# soap-disp-20210413-16Channel.net
KiCad netlist of a schematic drawn in EasyEDA
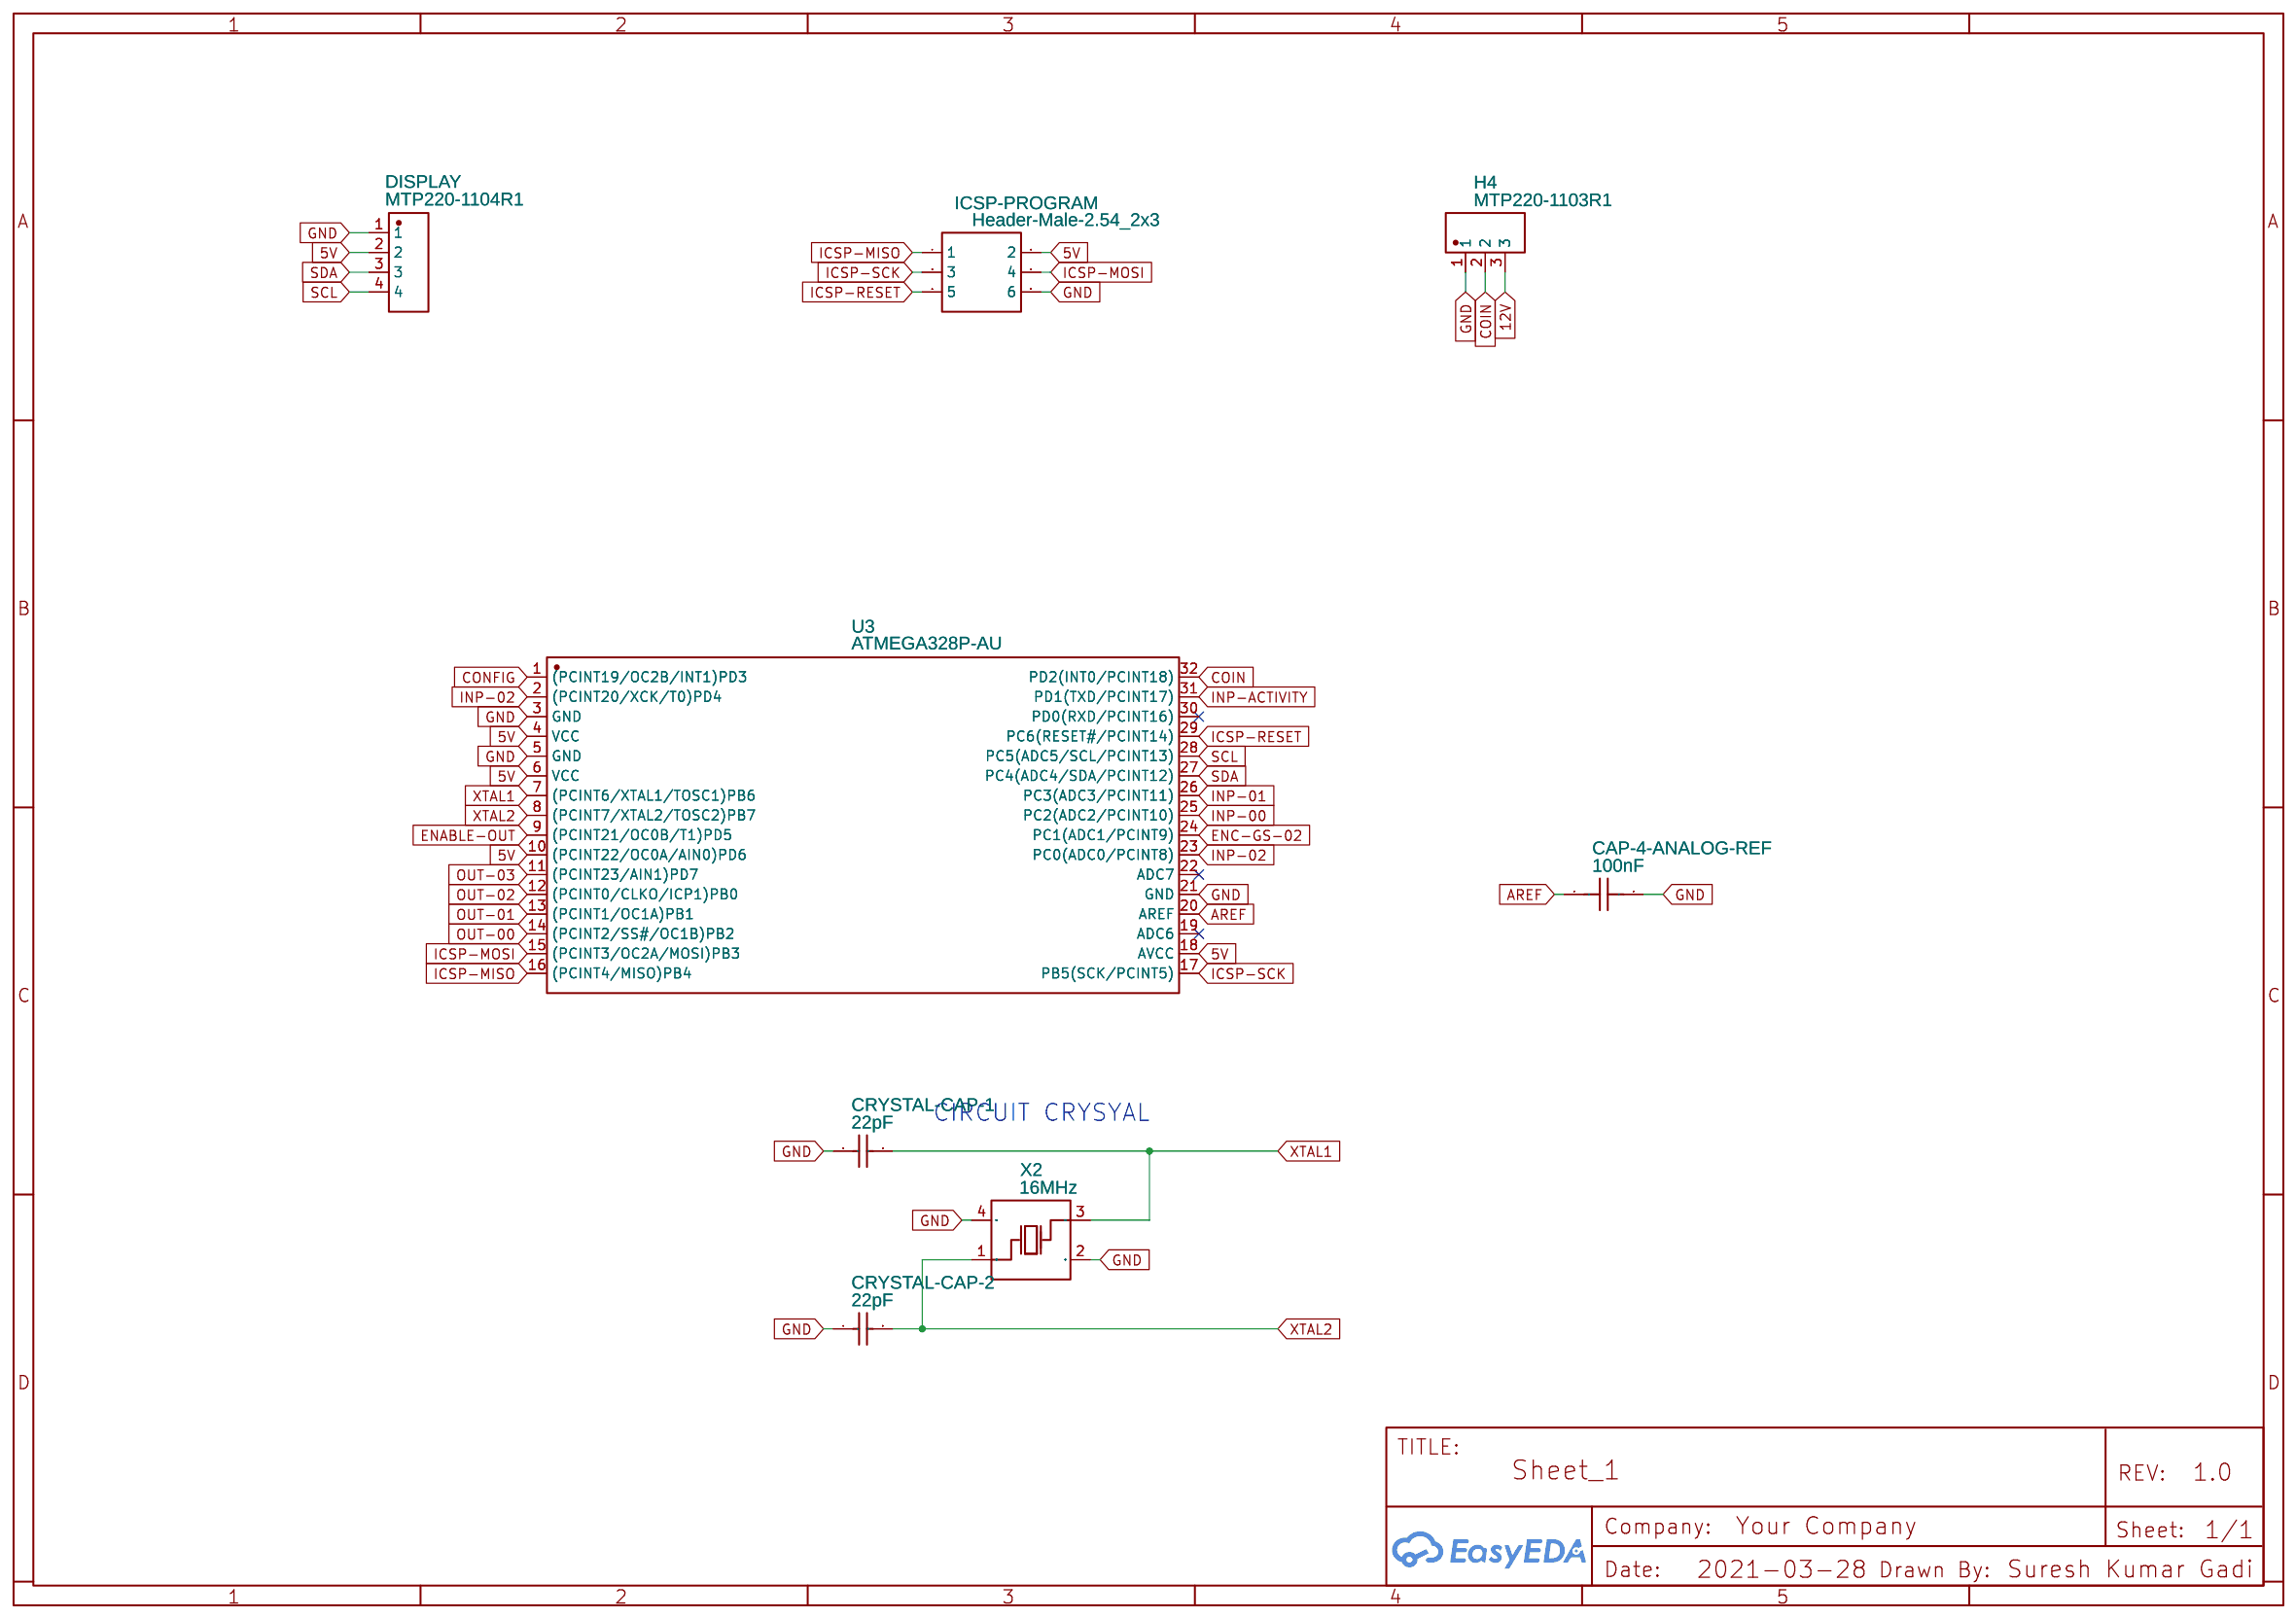
[diagram p0: Computer]
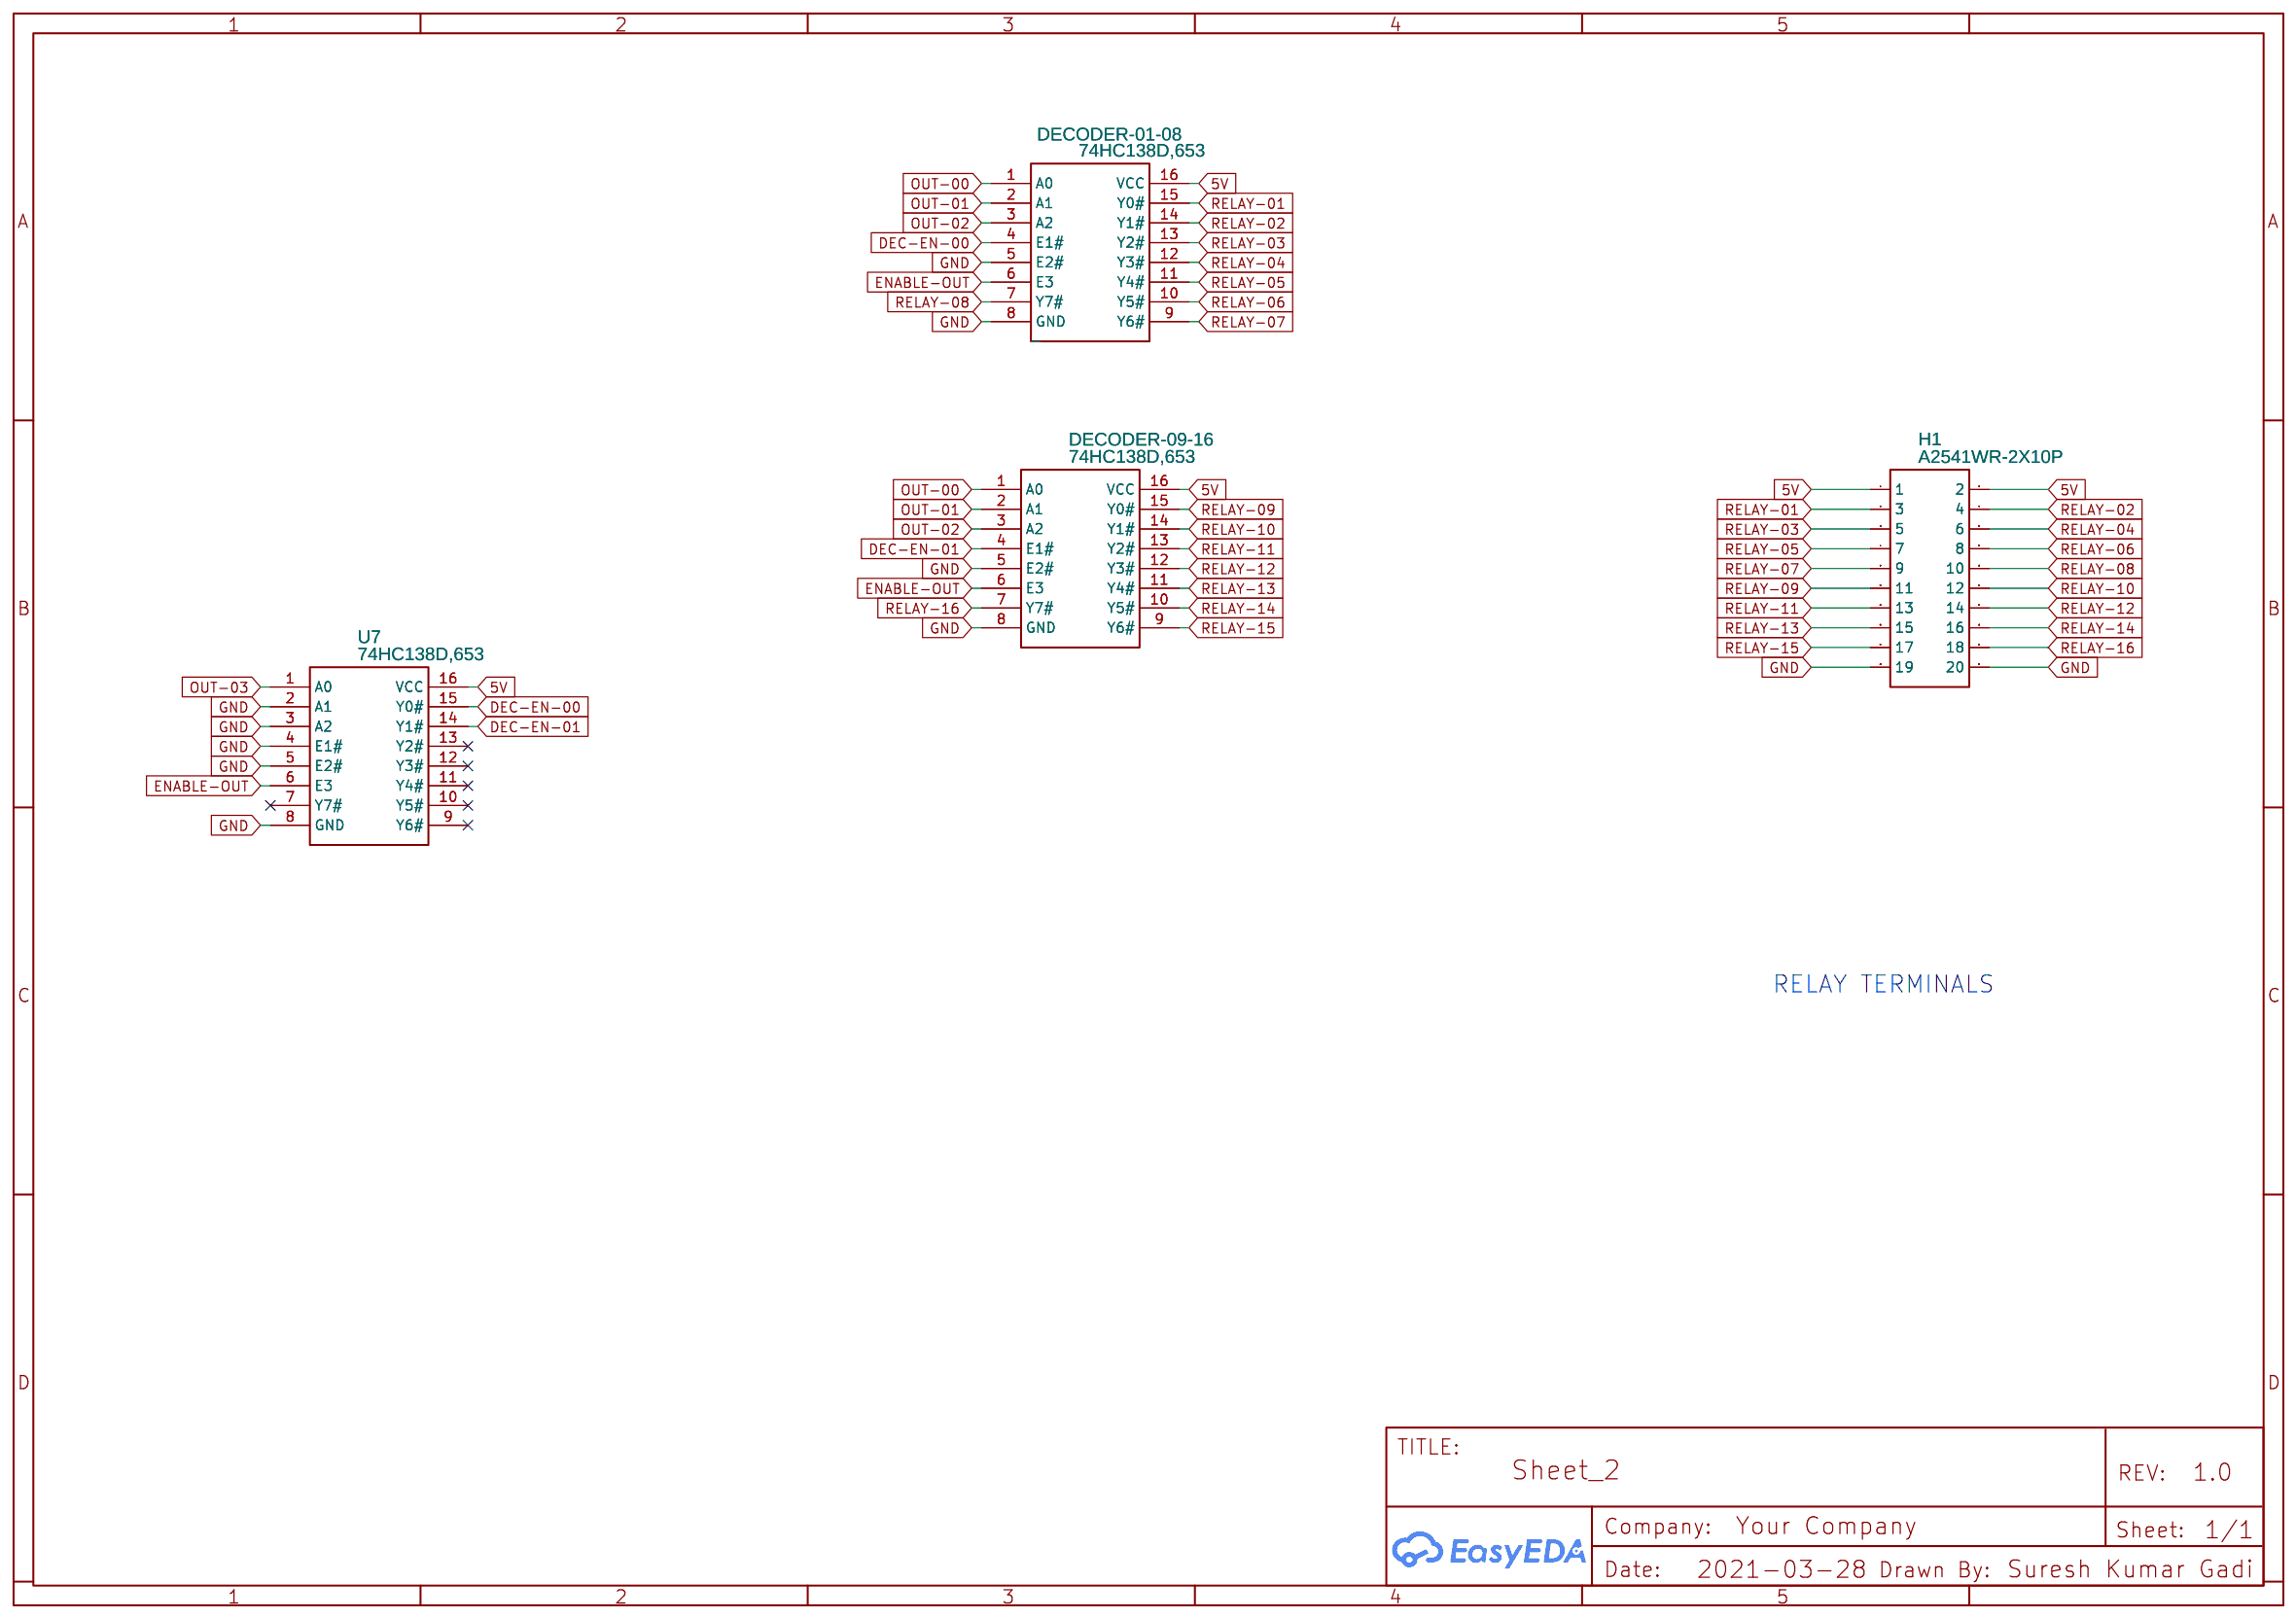
[diagram p1: Relays]
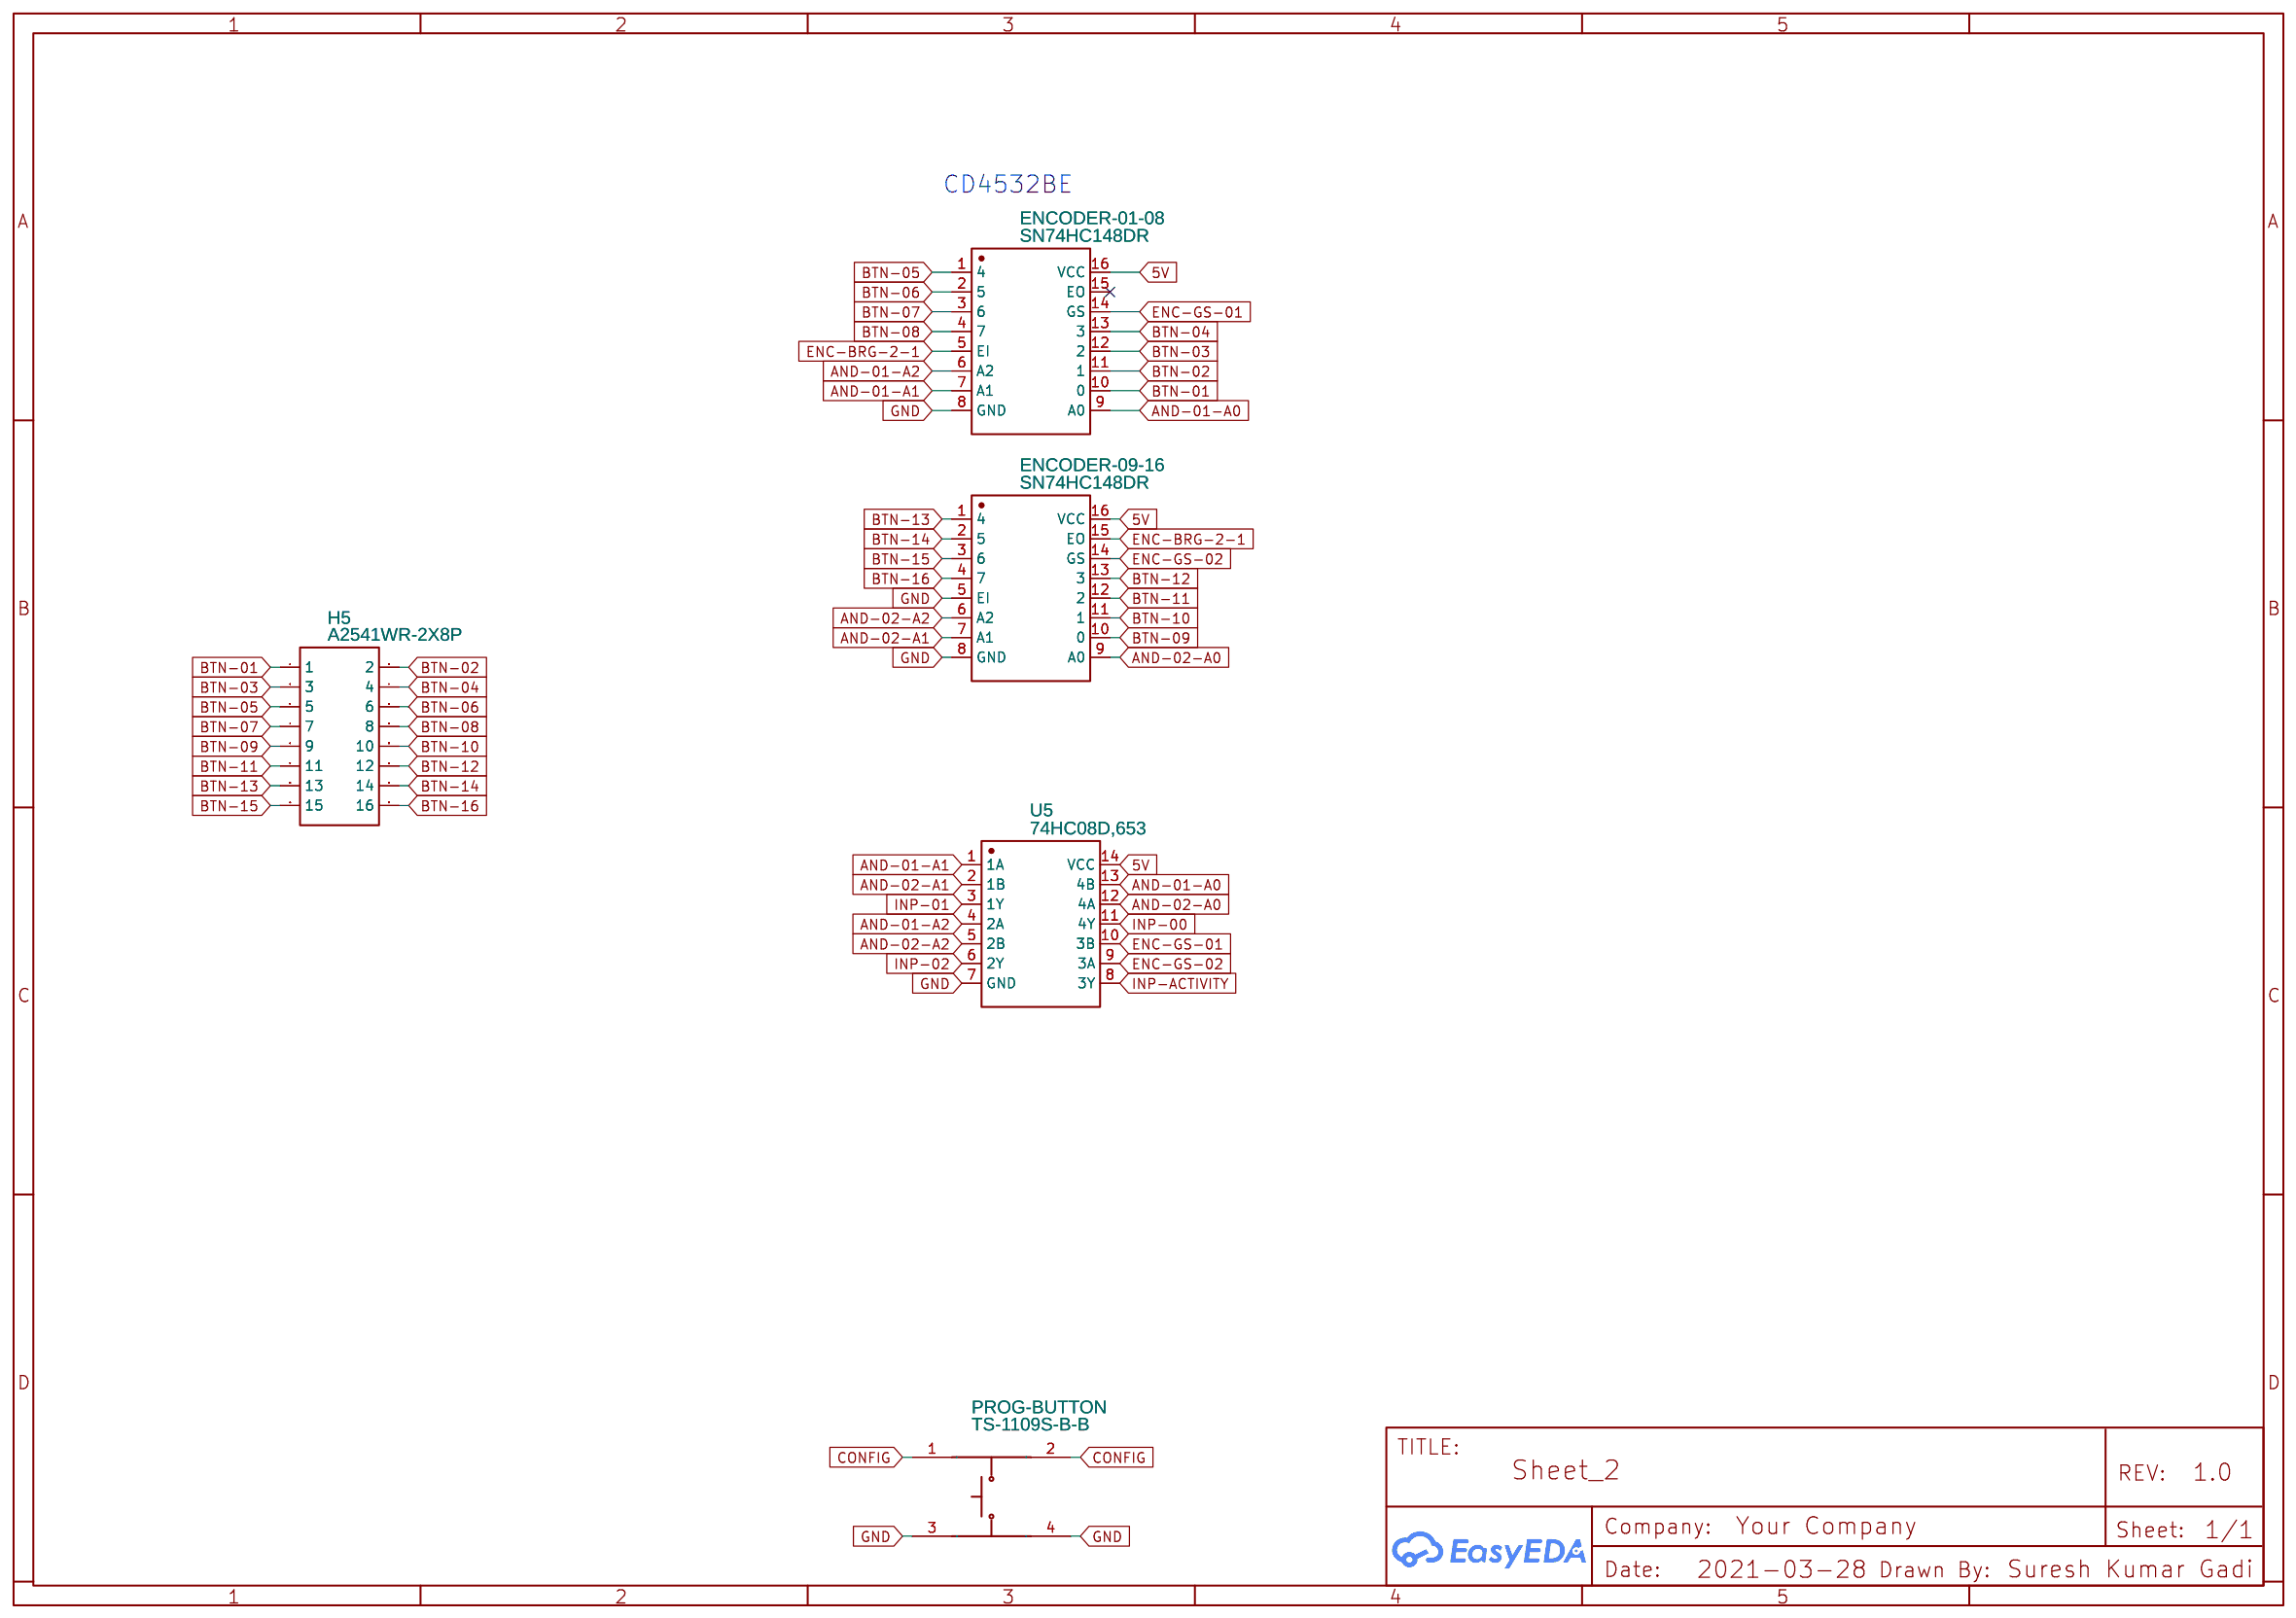
[diagram p2: Buttons]
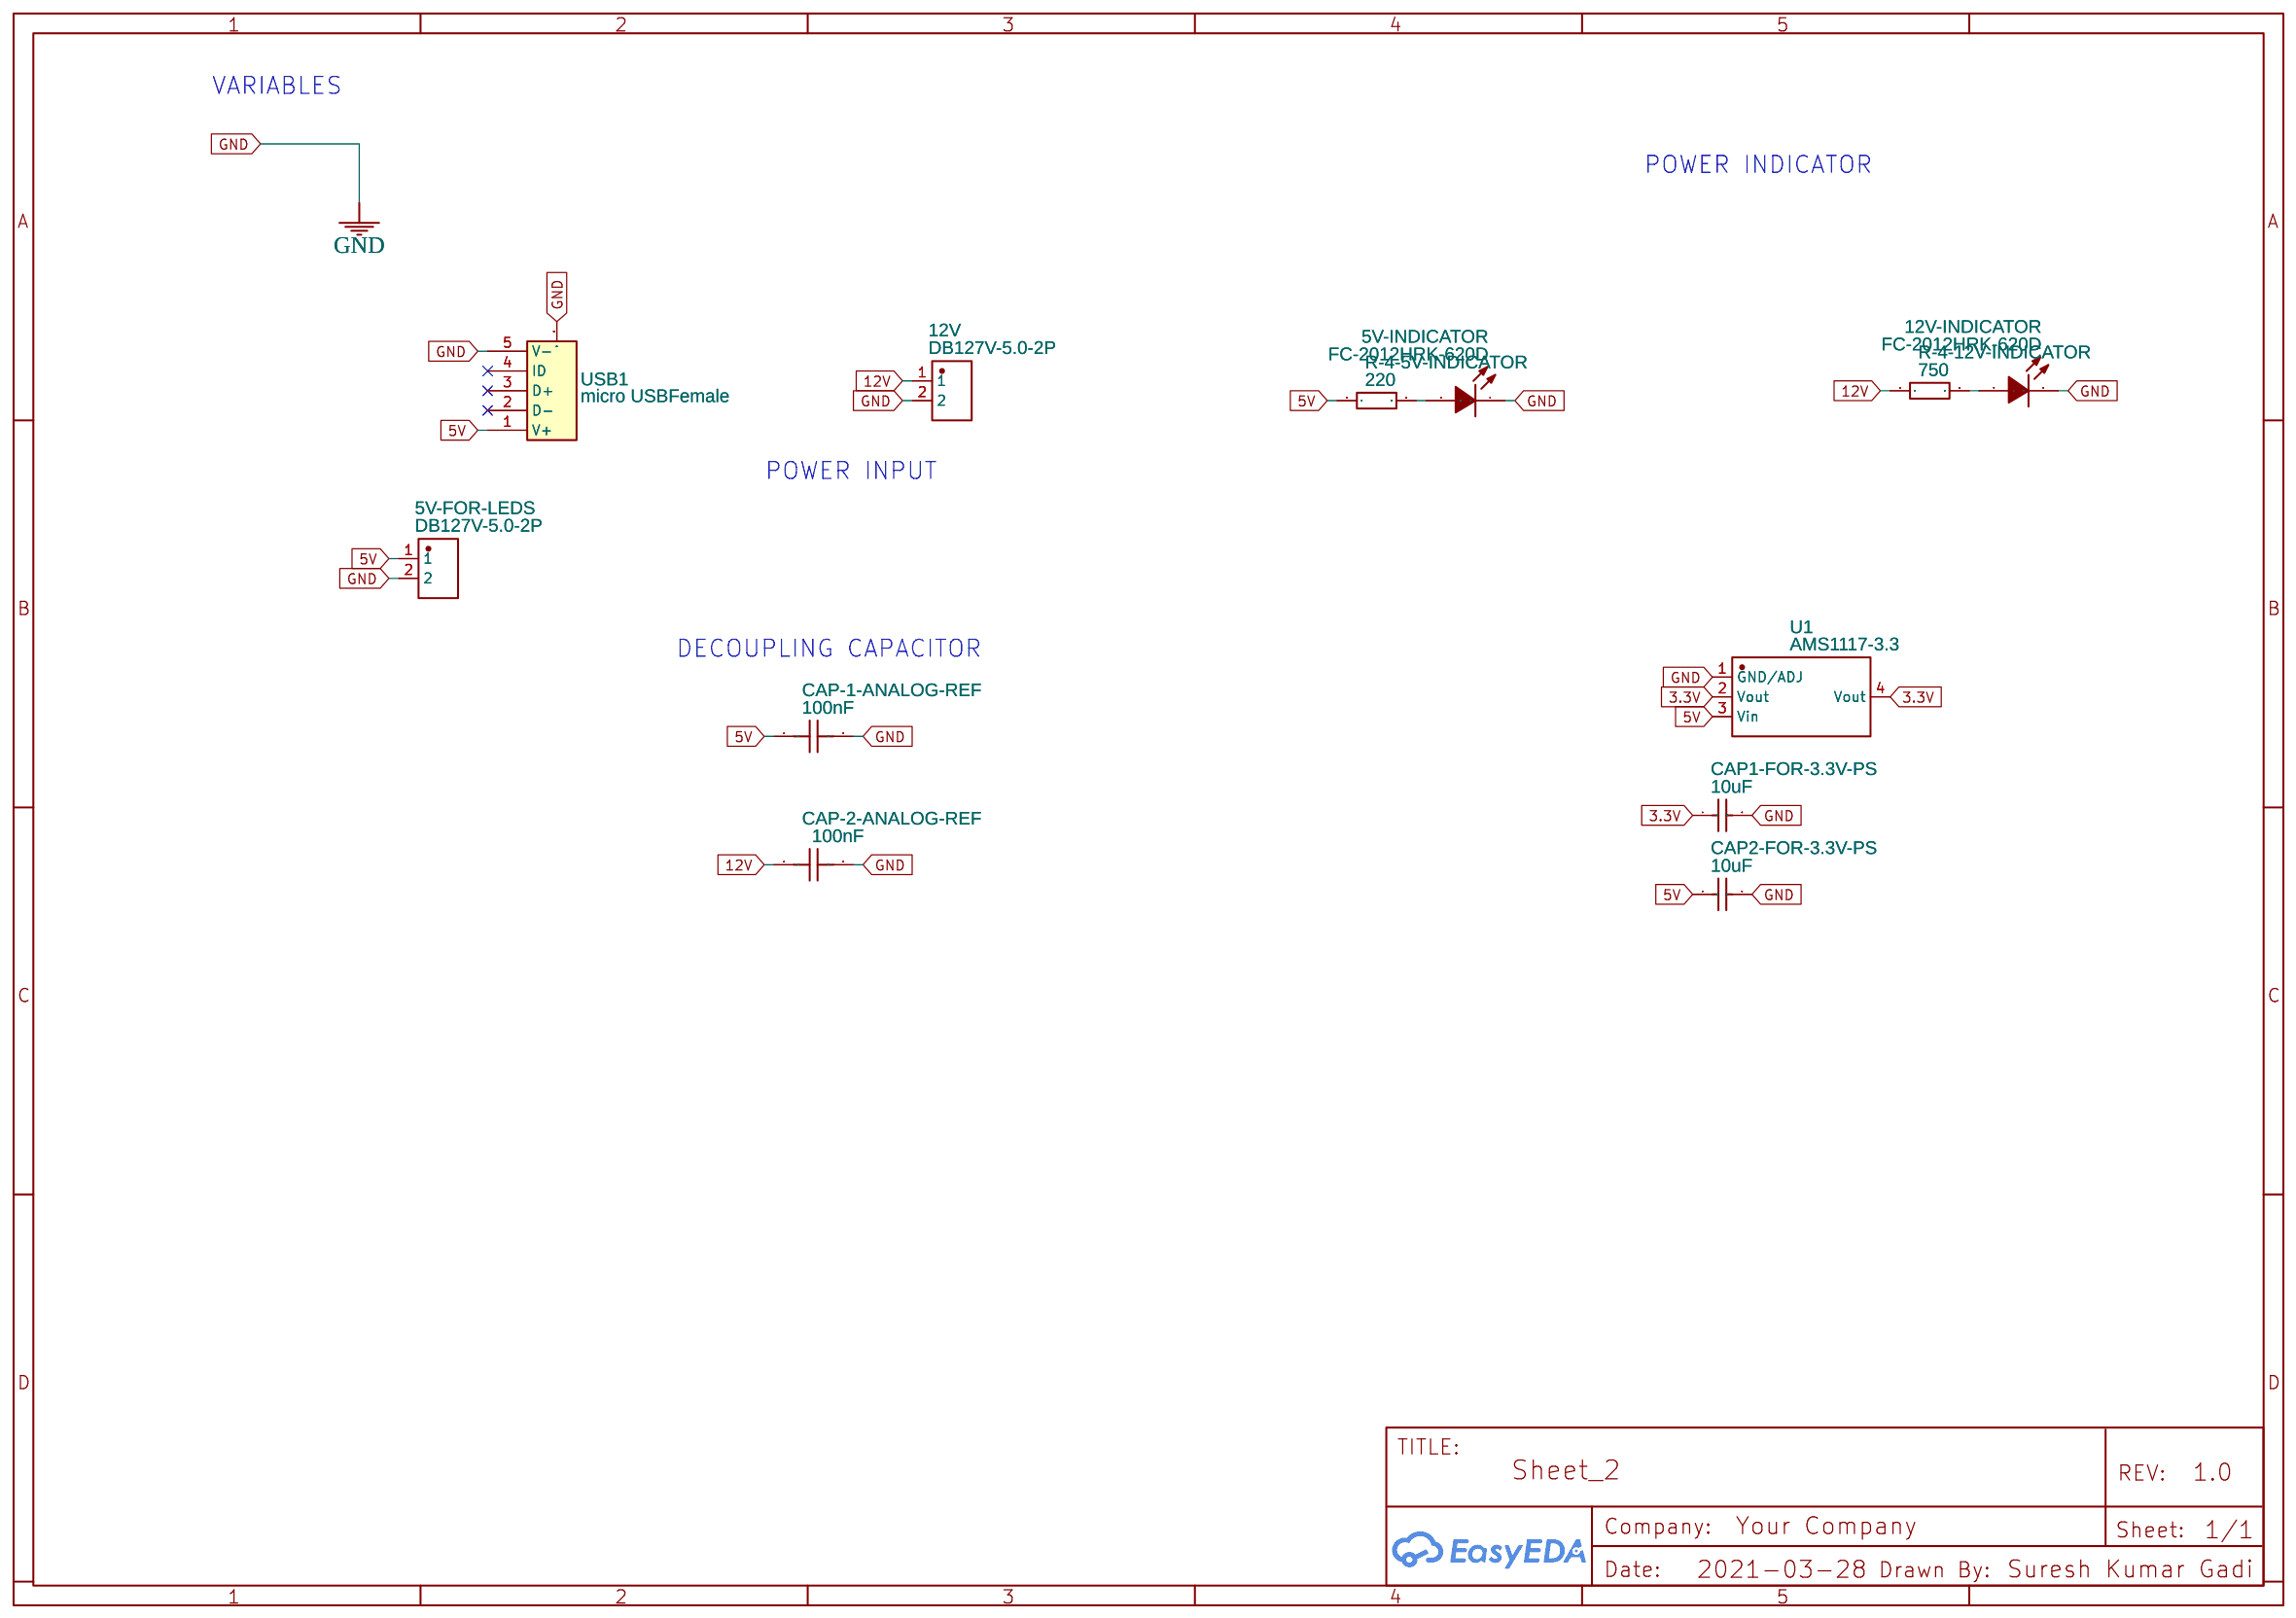
[diagram p3: Power]
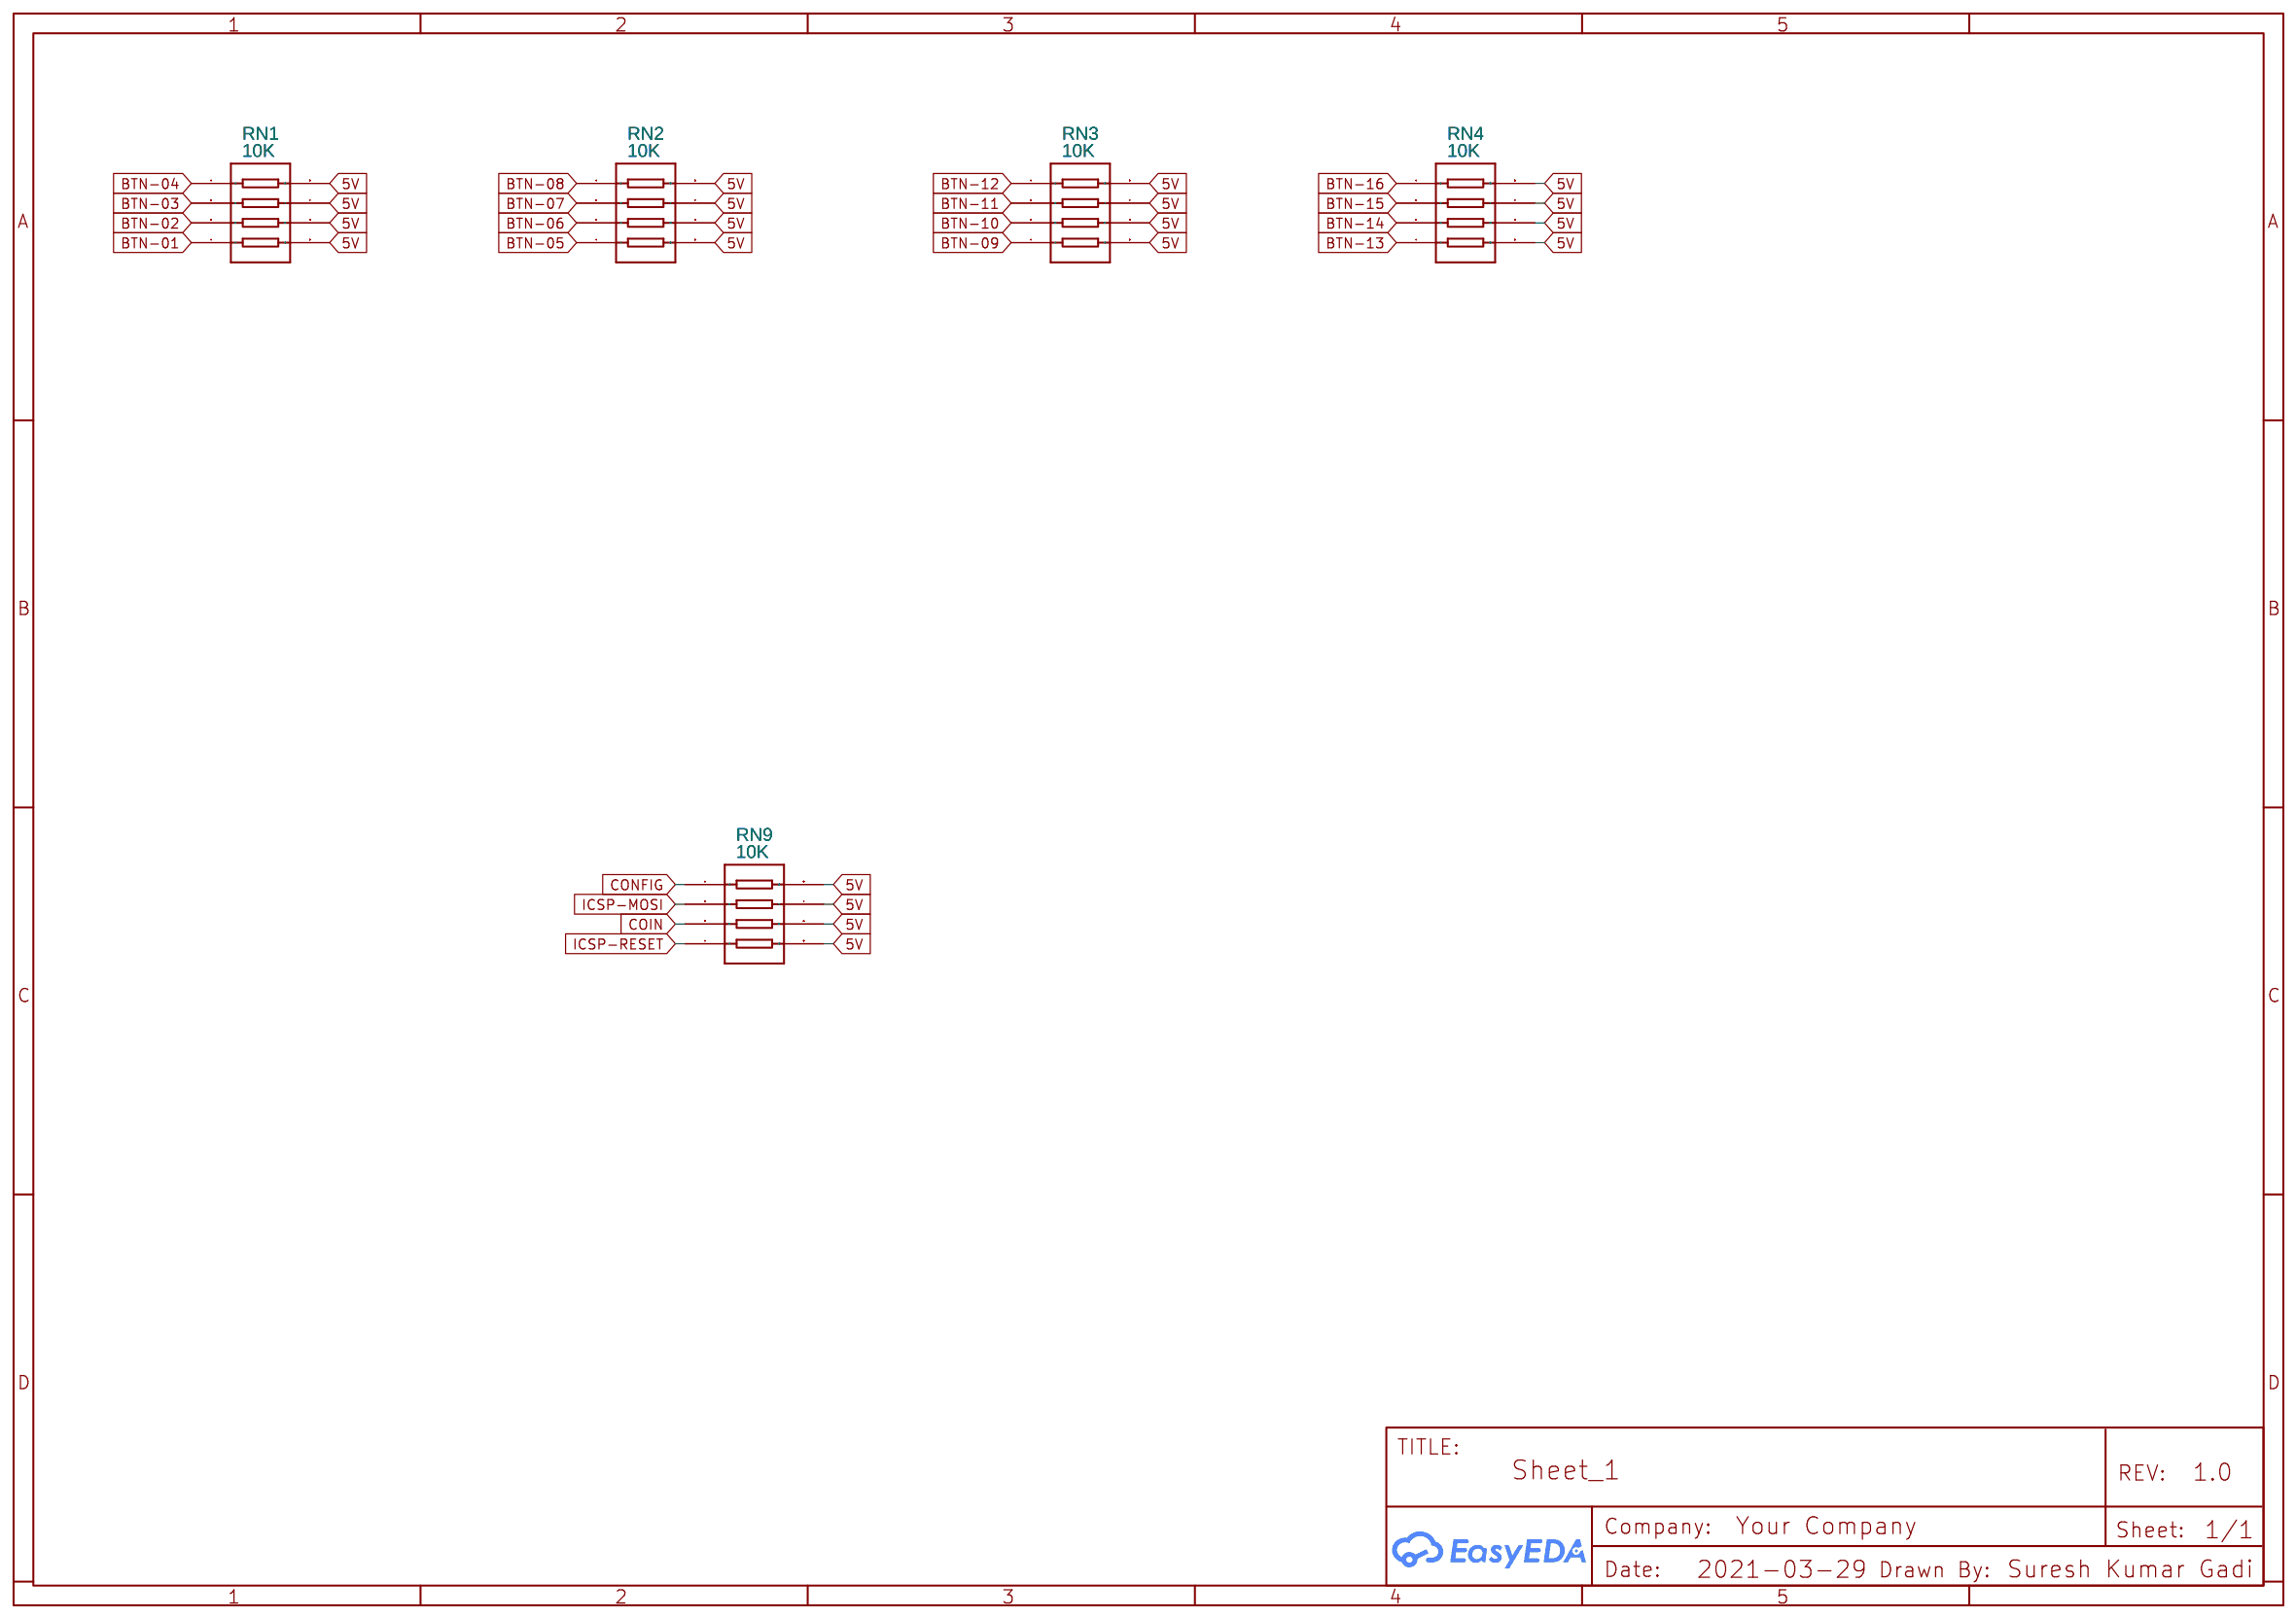
[diagram p4: Pull up-down]
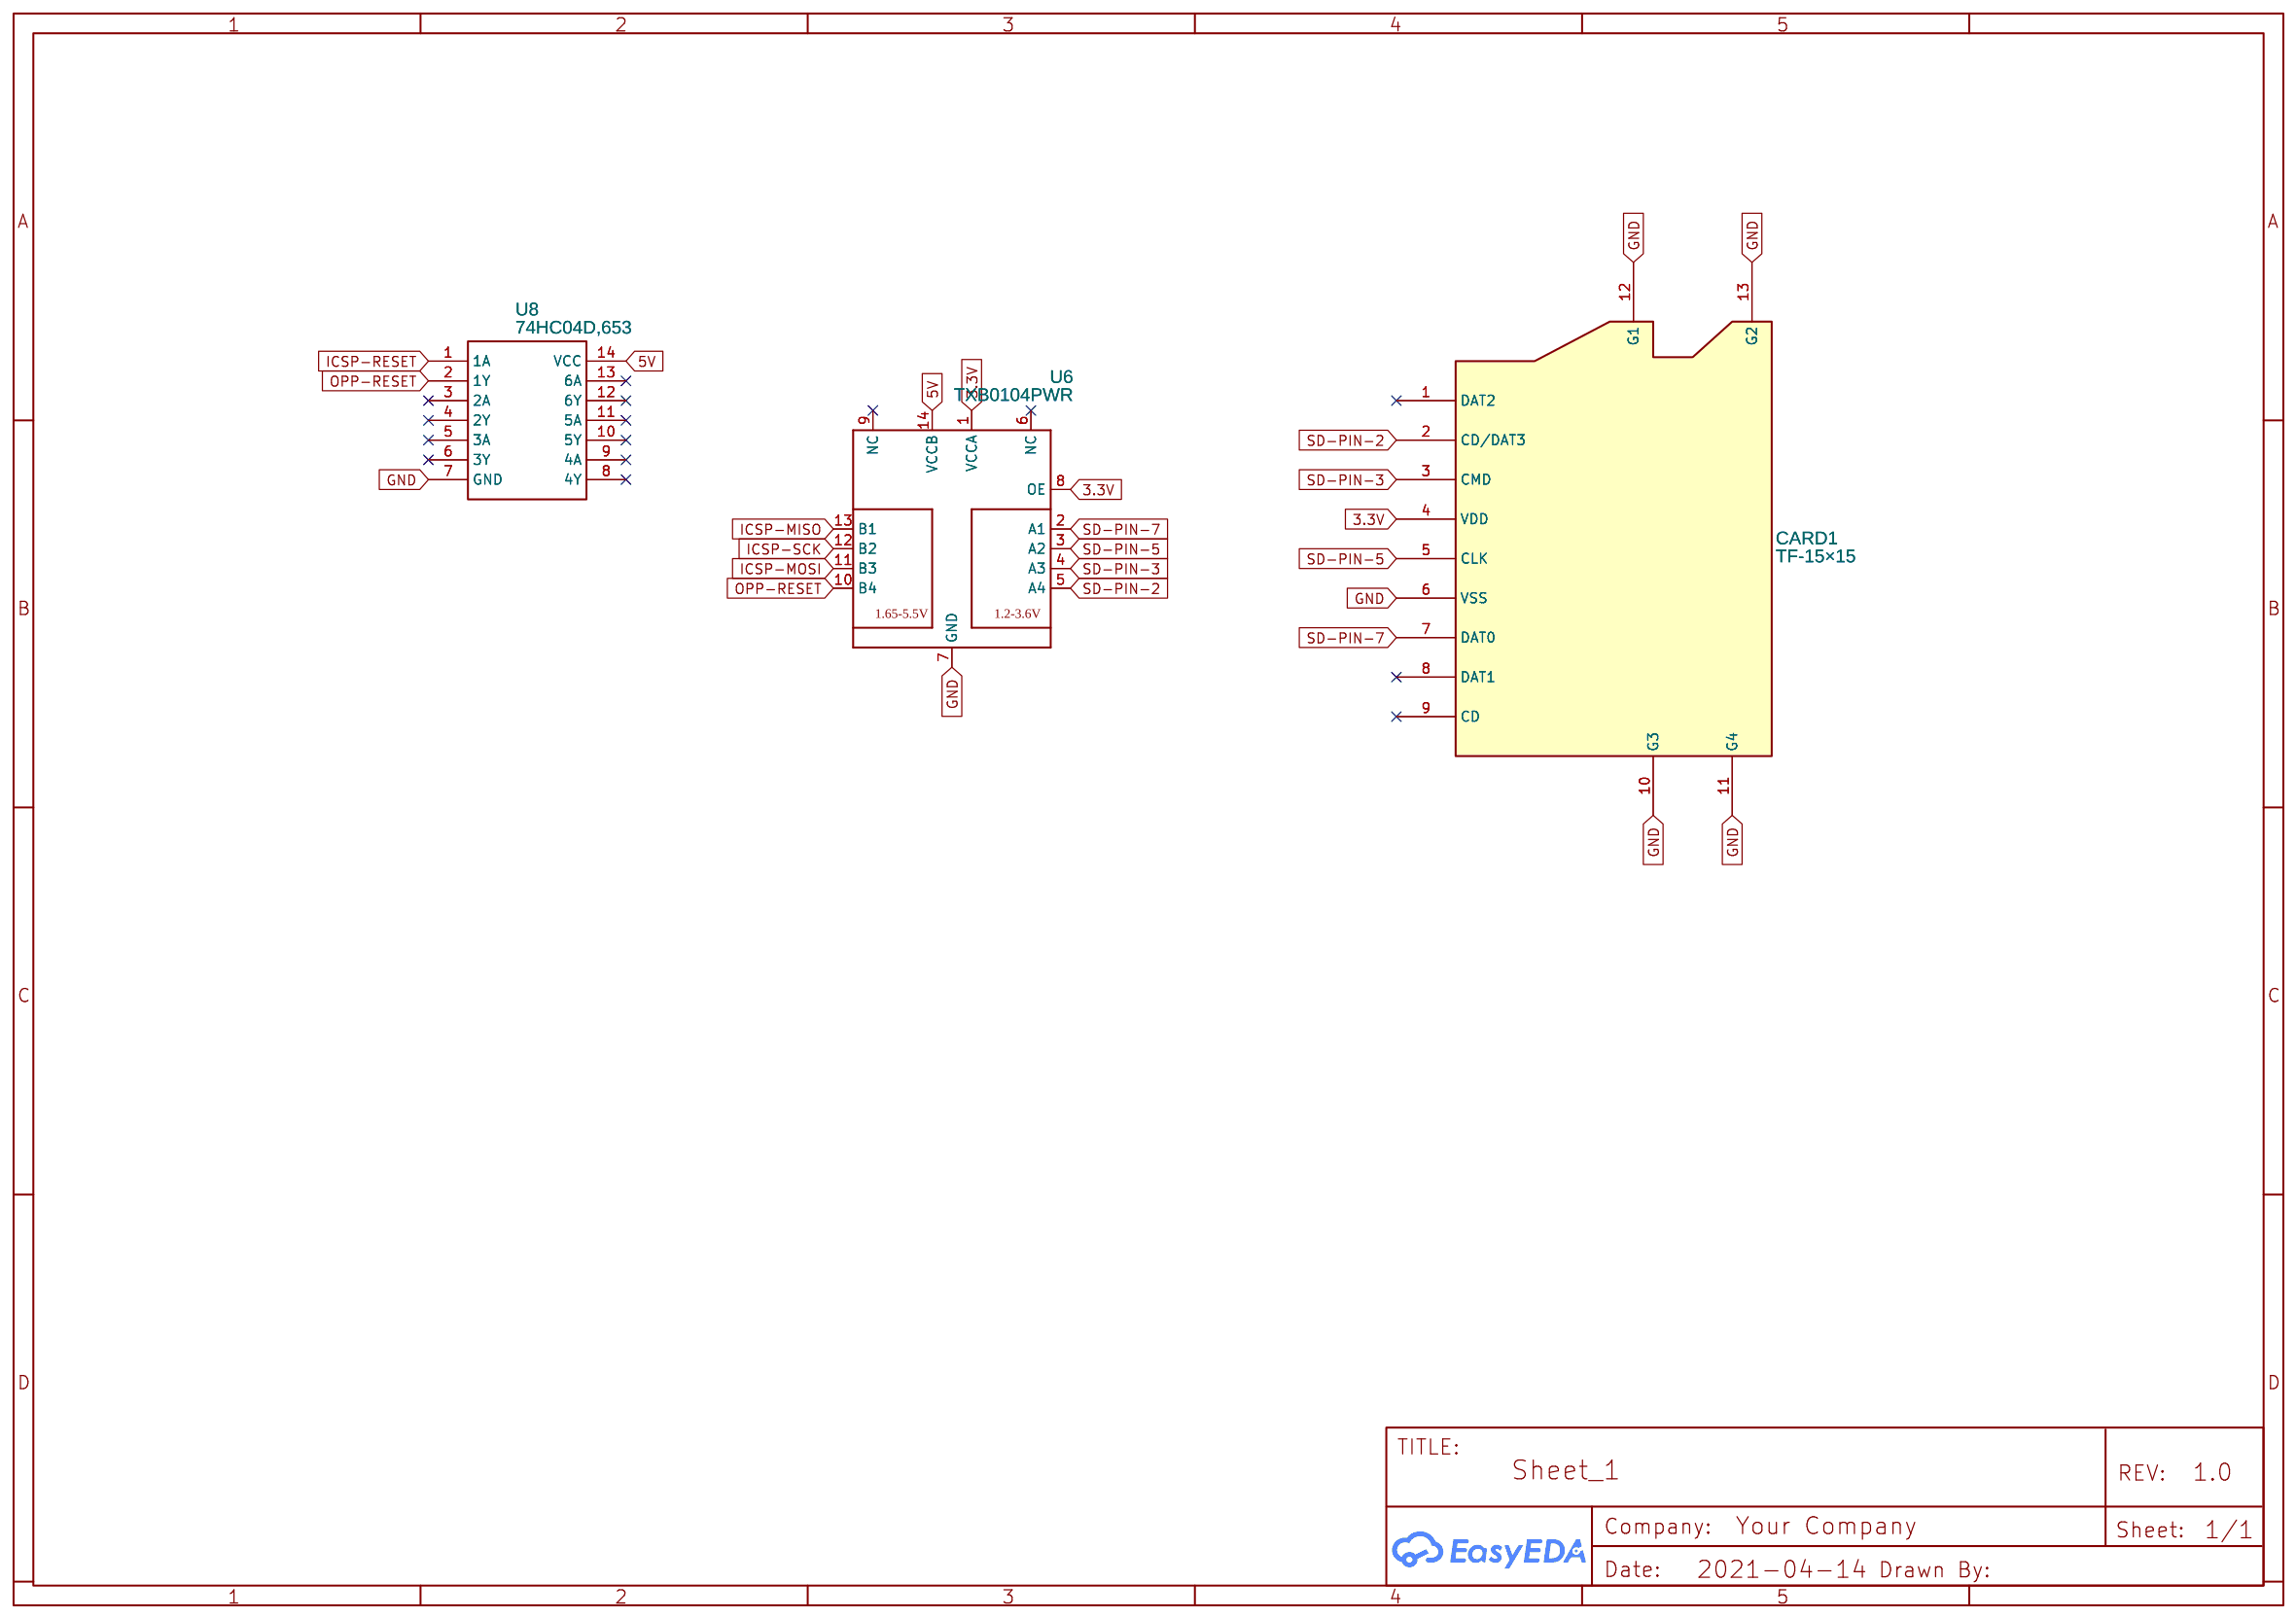
[diagram p5: SD Card]

(export (version "E")
  (design (tool "Eeschema 10.0.6"))
  (components
    (comp (ref "CAP-4-ANALOG-REF")
      (value "100nF")
      (fields
        (field (name "BOM_Manufacturer Part") "CC0603KRX7R9BB104")
        (field (name "BOM_Supplier Part") "C14663")
      )
      (libsource (lib "") (part "CC0603KRX7R9BB104"))
    )
    (comp (ref "CRYSTAL-CAP-1")
      (value "22pF")
      (fields
        (field (name "BOM_Manufacturer Part") "CL21C220JBANNNC")
        (field (name "BOM_Supplier Part") "C1804")
      )
      (libsource (lib "") (part "CL21C220JBANNNC"))
    )
    (comp (ref "CRYSTAL-CAP-2")
      (value "22pF")
      (fields
        (field (name "BOM_Manufacturer Part") "CL21C220JBANNNC")
        (field (name "BOM_Supplier Part") "C1804")
      )
      (libsource (lib "") (part "CL21C220JBANNNC"))
    )
    (comp (ref "DISPLAY")
      (value "MTP220-1104R1")
      (fields (field (name "BOM_Supplier Part") "C376098"))
      (libsource (lib "") (part "MTP220-1104R1"))
    )
    (comp (ref "H4")
      (value "MTP220-1103R1")
      (fields (field (name "BOM_Supplier Part") "C376097"))
      (libsource (lib "") (part "MTP220-1103R1"))
    )
    (comp (ref "ICSP-PROGRAM")
      (value "Header-Male-2.54_2x3")
      (fields (field (name "BOM_Supplier Part") "C65114"))
      (libsource (lib "") (part "Header-Male-2.54_2x3"))
    )
    (comp (ref "U3")
      (value "ATMEGA328P-AU")
      (fields (field (name "BOM_Supplier Part") "C14877"))
      (libsource (lib "") (part "ATMEGA328P-AU"))
    )
    (comp (ref "X2")
      (value "16MHz")
      (fields
        (field (name "BOM_Manufacturer Part") "X322516MLB4SI")
        (field (name "BOM_Supplier Part") "C13738")
      )
      (libsource (lib "") (part "X322516MLB4SI"))
    )
    (comp (ref "DECODER-01-08")
      (value "74HC138D,653")
      (fields (field (name "BOM_Supplier Part") "C5602"))
      (libsource (lib "") (part "74HC138D,653"))
    )
    (comp (ref "DECODER-09-16")
      (value "74HC138D,653")
      (fields (field (name "BOM_Supplier Part") "C5602"))
      (libsource (lib "") (part "74HC138D,653_2"))
    )
    (comp (ref "H1")
      (value "A2541WR-2X10P")
      (fields
        (field (name "BOM_Manufacturer Part") "A2541WR-2x10P")
        (field (name "BOM_Supplier Part") "C239341")
      )
      (libsource (lib "") (part "A2541WR-2X10P"))
    )
    (comp (ref "U7")
      (value "74HC138D,653")
      (fields (field (name "BOM_Supplier Part") "C5602"))
      (libsource (lib "") (part "74HC138D,653_1"))
    )
    (comp (ref "ENCODER-01-08")
      (value "SN74HC148DR")
      (fields (field (name "BOM_Supplier Part") "C6819"))
      (libsource (lib "") (part "SN74HC148DR_1"))
    )
    (comp (ref "ENCODER-09-16")
      (value "SN74HC148DR")
      (fields (field (name "BOM_Supplier Part") "C6819"))
      (libsource (lib "") (part "SN74HC148DR"))
    )
    (comp (ref "H5")
      (value "A2541WR-2X8P")
      (fields
        (field (name "BOM_Manufacturer Part") "A2541WR-2x8P")
        (field (name "BOM_Supplier Part") "C239339")
      )
      (libsource (lib "") (part "A2541WR-2X8P"))
    )
    (comp (ref "PROG-BUTTON")
      (value "TS-1109S-B-B")
      (fields (field (name "BOM_Supplier Part") "C480315"))
      (libsource (lib "") (part "TS-1109S-B-B"))
    )
    (comp (ref "U5")
      (value "74HC08D,653")
      (fields (field (name "BOM_Supplier Part") "C5593"))
      (libsource (lib "") (part "74HC08D,653"))
    )
    (comp (ref "5V-FOR-LEDS")
      (value "DB127V-5.0-2P")
      (fields (field (name "BOM_Supplier Part") "C395885"))
      (libsource (lib "") (part "DB127V-5.0-2P"))
    )
    (comp (ref "5V-INDICATOR")
      (value "FC-2012HRK-620D")
      (fields (field (name "BOM_Supplier Part") "C84256"))
      (libsource (lib "") (part "FC-2012HRK-620D"))
    )
    (comp (ref "12V")
      (value "DB127V-5.0-2P")
      (fields (field (name "BOM_Supplier Part") "C395885"))
      (libsource (lib "") (part "DB127V-5.0-2P_1"))
    )
    (comp (ref "12V-INDICATOR")
      (value "FC-2012HRK-620D")
      (fields (field (name "BOM_Supplier Part") "C84256"))
      (libsource (lib "") (part "FC-2012HRK-620D_1"))
    )
    (comp (ref "CAP-1-ANALOG-REF")
      (value "100nF")
      (fields
        (field (name "BOM_Manufacturer Part") "CC0603KRX7R9BB104")
        (field (name "BOM_Supplier Part") "C14663")
      )
      (libsource (lib "") (part "CC0603KRX7R9BB104_1"))
    )
    (comp (ref "CAP-2-ANALOG-REF")
      (value "100nF")
      (fields
        (field (name "BOM_Manufacturer Part") "CC0603KRX7R9BB104")
        (field (name "BOM_Supplier Part") "C14663")
      )
      (libsource (lib "") (part "CC0603KRX7R9BB104"))
    )
    (comp (ref "CAP1-FOR-3.3V-PS")
      (value "10uF")
      (fields
        (field (name "BOM_Manufacturer Part") "CL21A106KAYNNNE")
        (field (name "BOM_Supplier Part") "C15850")
      )
      (libsource (lib "") (part "CL21A106KAYNNNE"))
    )
    (comp (ref "CAP2-FOR-3.3V-PS")
      (value "10uF")
      (fields
        (field (name "BOM_Manufacturer Part") "CL21A106KAYNNNE")
        (field (name "BOM_Supplier Part") "C15850")
      )
      (libsource (lib "") (part "CL21A106KAYNNNE_1"))
    )
    (comp (ref "R-4-5V-INDICATOR")
      (value "220")
      (fields
        (field (name "BOM_Manufacturer Part") "0805W8F2200T5E")
        (field (name "BOM_Supplier Part") "C17557")
      )
      (libsource (lib "") (part "0805W8F2200T5E"))
    )
    (comp (ref "R-4-12V-INDICATOR")
      (value "750")
      (fields
        (field (name "BOM_Manufacturer Part") "1206W4F7500T5E")
        (field (name "BOM_Supplier Part") "C17985")
      )
      (libsource (lib "") (part "1206W4F7500T5E"))
    )
    (comp (ref "U1")
      (value "AMS1117-3.3")
      (fields (field (name "BOM_Supplier Part") "C6186"))
      (libsource (lib "") (part "AMS1117-3.3"))
    )
    (comp (ref "USB1")
      (value "micro USBFemale")
      (fields (field (name "BOM_Supplier Part") "C10418"))
      (libsource (lib "") (part "micro USBFemale"))
    )
    (comp (ref "RN1")
      (value "10K")
      (fields
        (field (name "BOM_Manufacturer Part") "4D03WGJ0103T5E")
        (field (name "BOM_Supplier Part") "C29718")
      )
      (libsource (lib "") (part "4D03WGJ0103T5E"))
    )
    (comp (ref "RN2")
      (value "10K")
      (fields
        (field (name "BOM_Manufacturer Part") "4D03WGJ0103T5E")
        (field (name "BOM_Supplier Part") "C29718")
      )
      (libsource (lib "") (part "4D03WGJ0103T5E"))
    )
    (comp (ref "RN3")
      (value "10K")
      (fields
        (field (name "BOM_Manufacturer Part") "4D03WGJ0103T5E")
        (field (name "BOM_Supplier Part") "C29718")
      )
      (libsource (lib "") (part "4D03WGJ0103T5E"))
    )
    (comp (ref "RN4")
      (value "10K")
      (fields
        (field (name "BOM_Manufacturer Part") "4D03WGJ0103T5E")
        (field (name "BOM_Supplier Part") "C29718")
      )
      (libsource (lib "") (part "4D03WGJ0103T5E"))
    )
    (comp (ref "RN9")
      (value "10K")
      (fields
        (field (name "BOM_Manufacturer Part") "4D03WGJ0103T5E")
        (field (name "BOM_Supplier Part") "C29718")
      )
      (libsource (lib "") (part "4D03WGJ0103T5E"))
    )
    (comp (ref "CARD1")
      (value "TF-15×15")
      (fields (field (name "BOM_Supplier Part") "C111196"))
      (libsource (lib "") (part "TF-15×15"))
    )
    (comp (ref "U6")
      (value "TXB0104PWR")
      (fields (field (name "BOM_Supplier Part") "C60708"))
      (libsource (lib "") (part "TXB0104PWR"))
    )
    (comp (ref "U8")
      (value "74HC04D,653")
      (fields (field (name "BOM_Supplier Part") "C5590"))
      (libsource (lib "") (part "74HC04D,653"))
    )
  )
  (nets
    (net (code "1") (name "3.3V") (class "Default")
      (node (ref "CAP1-FOR-3.3V-PS") (pin "1") (pinfunction "1_1") (pintype "input"))
      (node (ref "CARD1") (pin "4") (pinfunction "VDD_4") (pintype "input"))
      (node (ref "U1") (pin "2") (pinfunction "Vout_2") (pintype "unspecified"))
      (node (ref "U1") (pin "4") (pinfunction "Vout_4") (pintype "unspecified"))
      (node (ref "U6") (pin "1") (pinfunction "VCCA_1") (pintype "unspecified"))
      (node (ref "U6") (pin "8") (pinfunction "OE_8") (pintype "unspecified"))
    )
    (net (code "2") (name "5V") (class "Default")
      (node (ref "5V-FOR-LEDS") (pin "1") (pinfunction "1_1") (pintype "unspecified"))
      (node (ref "CAP-1-ANALOG-REF") (pin "1") (pinfunction "1_1") (pintype "unspecified"))
      (node (ref "CAP2-FOR-3.3V-PS") (pin "1") (pinfunction "1_1") (pintype "input"))
      (node (ref "DECODER-01-08") (pin "16") (pinfunction "VCC_16") (pintype "unspecified"))
      (node (ref "DECODER-09-16") (pin "16") (pinfunction "VCC_16") (pintype "unspecified"))
      (node (ref "DISPLAY") (pin "2") (pinfunction "2_2") (pintype "unspecified"))
      (node (ref "ENCODER-01-08") (pin "16") (pinfunction "VCC_16") (pintype "unspecified"))
      (node (ref "ENCODER-09-16") (pin "16") (pinfunction "VCC_16") (pintype "unspecified"))
      (node (ref "H1") (pin "1") (pinfunction "1_1") (pintype "unspecified"))
      (node (ref "H1") (pin "2") (pinfunction "2_2") (pintype "unspecified"))
      (node (ref "ICSP-PROGRAM") (pin "2") (pinfunction "2_2") (pintype "input"))
      (node (ref "R-4-5V-INDICATOR") (pin "1") (pinfunction "1_1") (pintype "input"))
      (node (ref "RN1") (pin "5") (pinfunction "5_5") (pintype "input"))
      (node (ref "RN1") (pin "6") (pinfunction "6_6") (pintype "input"))
      (node (ref "RN1") (pin "7") (pinfunction "7_7") (pintype "input"))
      (node (ref "RN1") (pin "8") (pinfunction "8_8") (pintype "input"))
      (node (ref "RN2") (pin "5") (pinfunction "5_5") (pintype "input"))
      (node (ref "RN2") (pin "6") (pinfunction "6_6") (pintype "input"))
      (node (ref "RN2") (pin "7") (pinfunction "7_7") (pintype "input"))
      (node (ref "RN2") (pin "8") (pinfunction "8_8") (pintype "input"))
      (node (ref "RN3") (pin "5") (pinfunction "5_5") (pintype "input"))
      (node (ref "RN3") (pin "6") (pinfunction "6_6") (pintype "input"))
      (node (ref "RN3") (pin "7") (pinfunction "7_7") (pintype "input"))
      (node (ref "RN3") (pin "8") (pinfunction "8_8") (pintype "input"))
      (node (ref "RN4") (pin "5") (pinfunction "5_5") (pintype "input"))
      (node (ref "RN4") (pin "6") (pinfunction "6_6") (pintype "input"))
      (node (ref "RN4") (pin "7") (pinfunction "7_7") (pintype "input"))
      (node (ref "RN4") (pin "8") (pinfunction "8_8") (pintype "input"))
      (node (ref "RN9") (pin "5") (pinfunction "5_5") (pintype "input"))
      (node (ref "RN9") (pin "6") (pinfunction "6_6") (pintype "input"))
      (node (ref "RN9") (pin "7") (pinfunction "7_7") (pintype "input"))
      (node (ref "RN9") (pin "8") (pinfunction "8_8") (pintype "input"))
      (node (ref "U1") (pin "3") (pinfunction "Vin_3") (pintype "unspecified"))
      (node (ref "U3") (pin "10") (pinfunction "(PCINT22/OC0A/AIN0)PD6_10") (pintype "unspecified"))
      (node (ref "U3") (pin "18") (pinfunction "AVCC_18") (pintype "unspecified"))
      (node (ref "U3") (pin "4") (pinfunction "VCC_4") (pintype "unspecified"))
      (node (ref "U3") (pin "6") (pinfunction "VCC_6") (pintype "unspecified"))
      (node (ref "U5") (pin "14") (pinfunction "VCC_14") (pintype "unspecified"))
      (node (ref "U6") (pin "14") (pinfunction "VCCB_14") (pintype "unspecified"))
      (node (ref "U7") (pin "16") (pinfunction "VCC_16") (pintype "unspecified"))
      (node (ref "U8") (pin "14") (pinfunction "VCC_14") (pintype "unspecified"))
      (node (ref "USB1") (pin "1") (pinfunction "V+_1") (pintype "unspecified"))
    )
    (net (code "3") (name "12V") (class "Default")
      (node (ref "12V") (pin "1") (pinfunction "1_1") (pintype "unspecified"))
      (node (ref "CAP-2-ANALOG-REF") (pin "1") (pinfunction "1_1") (pintype "unspecified"))
      (node (ref "H4") (pin "3") (pinfunction "3_3") (pintype "unspecified"))
      (node (ref "R-4-12V-INDICATOR") (pin "1") (pinfunction "1_1") (pintype "input"))
    )
    (net (code "4") (name "AND-01-A0") (class "Default")
      (node (ref "ENCODER-01-08") (pin "9") (pinfunction "A0_9") (pintype "unspecified"))
      (node (ref "U5") (pin "13") (pinfunction "4B_13") (pintype "unspecified"))
    )
    (net (code "5") (name "AND-01-A1") (class "Default")
      (node (ref "ENCODER-01-08") (pin "7") (pinfunction "A1_7") (pintype "unspecified"))
      (node (ref "U5") (pin "1") (pinfunction "1A_1") (pintype "unspecified"))
    )
    (net (code "6") (name "AND-01-A2") (class "Default")
      (node (ref "ENCODER-01-08") (pin "6") (pinfunction "A2_6") (pintype "unspecified"))
      (node (ref "U5") (pin "4") (pinfunction "2A_4") (pintype "unspecified"))
    )
    (net (code "7") (name "AND-02-A0") (class "Default")
      (node (ref "ENCODER-09-16") (pin "9") (pinfunction "A0_9") (pintype "unspecified"))
      (node (ref "U5") (pin "12") (pinfunction "4A_12") (pintype "unspecified"))
    )
    (net (code "8") (name "AND-02-A1") (class "Default")
      (node (ref "ENCODER-09-16") (pin "7") (pinfunction "A1_7") (pintype "unspecified"))
      (node (ref "U5") (pin "2") (pinfunction "1B_2") (pintype "unspecified"))
    )
    (net (code "9") (name "AND-02-A2") (class "Default")
      (node (ref "ENCODER-09-16") (pin "6") (pinfunction "A2_6") (pintype "unspecified"))
      (node (ref "U5") (pin "5") (pinfunction "2B_5") (pintype "unspecified"))
    )
    (net (code "10") (name "AREF") (class "Default")
      (node (ref "CAP-4-ANALOG-REF") (pin "1") (pinfunction "1_1") (pintype "unspecified"))
      (node (ref "U3") (pin "20") (pinfunction "AREF_20") (pintype "unspecified"))
    )
    (net (code "11") (name "BTN-01") (class "Default")
      (node (ref "ENCODER-01-08") (pin "10") (pinfunction "0_10") (pintype "unspecified"))
      (node (ref "H5") (pin "1") (pinfunction "1_1") (pintype "unspecified"))
      (node (ref "RN1") (pin "4") (pinfunction "4_4") (pintype "input"))
    )
    (net (code "12") (name "BTN-02") (class "Default")
      (node (ref "ENCODER-01-08") (pin "11") (pinfunction "1_11") (pintype "unspecified"))
      (node (ref "H5") (pin "2") (pinfunction "2_2") (pintype "unspecified"))
      (node (ref "RN1") (pin "3") (pinfunction "3_3") (pintype "input"))
    )
    (net (code "13") (name "BTN-03") (class "Default")
      (node (ref "ENCODER-01-08") (pin "12") (pinfunction "2_12") (pintype "unspecified"))
      (node (ref "H5") (pin "3") (pinfunction "3_3") (pintype "unspecified"))
      (node (ref "RN1") (pin "2") (pinfunction "2_2") (pintype "input"))
    )
    (net (code "14") (name "BTN-04") (class "Default")
      (node (ref "ENCODER-01-08") (pin "13") (pinfunction "3_13") (pintype "unspecified"))
      (node (ref "H5") (pin "4") (pinfunction "4_4") (pintype "unspecified"))
      (node (ref "RN1") (pin "1") (pinfunction "1_1") (pintype "input"))
    )
    (net (code "15") (name "BTN-05") (class "Default")
      (node (ref "ENCODER-01-08") (pin "1") (pinfunction "4_1") (pintype "unspecified"))
      (node (ref "H5") (pin "5") (pinfunction "5_5") (pintype "unspecified"))
      (node (ref "RN2") (pin "4") (pinfunction "4_4") (pintype "input"))
    )
    (net (code "16") (name "BTN-06") (class "Default")
      (node (ref "ENCODER-01-08") (pin "2") (pinfunction "5_2") (pintype "unspecified"))
      (node (ref "H5") (pin "6") (pinfunction "6_6") (pintype "unspecified"))
      (node (ref "RN2") (pin "3") (pinfunction "3_3") (pintype "input"))
    )
    (net (code "17") (name "BTN-07") (class "Default")
      (node (ref "ENCODER-01-08") (pin "3") (pinfunction "6_3") (pintype "unspecified"))
      (node (ref "H5") (pin "7") (pinfunction "7_7") (pintype "unspecified"))
      (node (ref "RN2") (pin "2") (pinfunction "2_2") (pintype "input"))
    )
    (net (code "18") (name "BTN-08") (class "Default")
      (node (ref "ENCODER-01-08") (pin "4") (pinfunction "7_4") (pintype "unspecified"))
      (node (ref "H5") (pin "8") (pinfunction "8_8") (pintype "unspecified"))
      (node (ref "RN2") (pin "1") (pinfunction "1_1") (pintype "input"))
    )
    (net (code "19") (name "BTN-09") (class "Default")
      (node (ref "ENCODER-09-16") (pin "10") (pinfunction "0_10") (pintype "unspecified"))
      (node (ref "H5") (pin "9") (pinfunction "9_9") (pintype "unspecified"))
      (node (ref "RN3") (pin "4") (pinfunction "4_4") (pintype "input"))
    )
    (net (code "20") (name "BTN-10") (class "Default")
      (node (ref "ENCODER-09-16") (pin "11") (pinfunction "1_11") (pintype "unspecified"))
      (node (ref "H5") (pin "10") (pinfunction "10_10") (pintype "unspecified"))
      (node (ref "RN3") (pin "3") (pinfunction "3_3") (pintype "input"))
    )
    (net (code "21") (name "BTN-11") (class "Default")
      (node (ref "ENCODER-09-16") (pin "12") (pinfunction "2_12") (pintype "unspecified"))
      (node (ref "H5") (pin "11") (pinfunction "11_11") (pintype "unspecified"))
      (node (ref "RN3") (pin "2") (pinfunction "2_2") (pintype "input"))
    )
    (net (code "22") (name "BTN-12") (class "Default")
      (node (ref "ENCODER-09-16") (pin "13") (pinfunction "3_13") (pintype "unspecified"))
      (node (ref "H5") (pin "12") (pinfunction "12_12") (pintype "unspecified"))
      (node (ref "RN3") (pin "1") (pinfunction "1_1") (pintype "input"))
    )
    (net (code "23") (name "BTN-13") (class "Default")
      (node (ref "ENCODER-09-16") (pin "1") (pinfunction "4_1") (pintype "unspecified"))
      (node (ref "H5") (pin "13") (pinfunction "13_13") (pintype "unspecified"))
      (node (ref "RN4") (pin "4") (pinfunction "4_4") (pintype "input"))
    )
    (net (code "24") (name "BTN-14") (class "Default")
      (node (ref "ENCODER-09-16") (pin "2") (pinfunction "5_2") (pintype "unspecified"))
      (node (ref "H5") (pin "14") (pinfunction "14_14") (pintype "unspecified"))
      (node (ref "RN4") (pin "3") (pinfunction "3_3") (pintype "input"))
    )
    (net (code "25") (name "BTN-15") (class "Default")
      (node (ref "ENCODER-09-16") (pin "3") (pinfunction "6_3") (pintype "unspecified"))
      (node (ref "H5") (pin "15") (pinfunction "15_15") (pintype "unspecified"))
      (node (ref "RN4") (pin "2") (pinfunction "2_2") (pintype "input"))
    )
    (net (code "26") (name "BTN-16") (class "Default")
      (node (ref "ENCODER-09-16") (pin "4") (pinfunction "7_4") (pintype "unspecified"))
      (node (ref "H5") (pin "16") (pinfunction "16_16") (pintype "unspecified"))
      (node (ref "RN4") (pin "1") (pinfunction "1_1") (pintype "input"))
    )
    (net (code "27") (name "COIN") (class "Default")
      (node (ref "H4") (pin "2") (pinfunction "2_2") (pintype "unspecified"))
      (node (ref "RN9") (pin "3") (pinfunction "3_3") (pintype "input"))
      (node (ref "U3") (pin "32") (pinfunction "PD2(INT0/PCINT18)_32") (pintype "unspecified"))
    )
    (net (code "28") (name "CONFIG") (class "Default")
      (node (ref "PROG-BUTTON") (pin "1") (pinfunction "1_1") (pintype "unspecified"))
      (node (ref "PROG-BUTTON") (pin "2") (pinfunction "2_2") (pintype "unspecified"))
      (node (ref "RN9") (pin "1") (pinfunction "1_1") (pintype "input"))
      (node (ref "U3") (pin "1") (pinfunction "(PCINT19/OC2B/INT1)PD3_1") (pintype "unspecified"))
    )
    (net (code "29") (name "DEC-EN-00") (class "Default")
      (node (ref "DECODER-01-08") (pin "4") (pinfunction "E1#_4") (pintype "unspecified"))
      (node (ref "U7") (pin "15") (pinfunction "Y0#_15") (pintype "unspecified"))
    )
    (net (code "30") (name "DEC-EN-01") (class "Default")
      (node (ref "DECODER-09-16") (pin "4") (pinfunction "E1#_4") (pintype "unspecified"))
      (node (ref "U7") (pin "14") (pinfunction "Y1#_14") (pintype "unspecified"))
    )
    (net (code "31") (name "ENABLE-OUT") (class "Default")
      (node (ref "DECODER-01-08") (pin "6") (pinfunction "E3_6") (pintype "unspecified"))
      (node (ref "DECODER-09-16") (pin "6") (pinfunction "E3_6") (pintype "unspecified"))
      (node (ref "U3") (pin "9") (pinfunction "(PCINT21/OC0B/T1)PD5_9") (pintype "unspecified"))
      (node (ref "U7") (pin "6") (pinfunction "E3_6") (pintype "unspecified"))
    )
    (net (code "32") (name "ENC-BRG-2-1") (class "Default")
      (node (ref "ENCODER-01-08") (pin "5") (pinfunction "EI_5") (pintype "unspecified"))
      (node (ref "ENCODER-09-16") (pin "15") (pinfunction "EO_15") (pintype "unspecified"))
    )
    (net (code "33") (name "ENC-GS-01") (class "Default")
      (node (ref "ENCODER-01-08") (pin "14") (pinfunction "GS_14") (pintype "unspecified"))
      (node (ref "U5") (pin "10") (pinfunction "3B_10") (pintype "unspecified"))
    )
    (net (code "34") (name "ENC-GS-02") (class "Default")
      (node (ref "ENCODER-09-16") (pin "14") (pinfunction "GS_14") (pintype "unspecified"))
      (node (ref "U3") (pin "24") (pinfunction "PC1(ADC1/PCINT9)_24") (pintype "unspecified"))
      (node (ref "U5") (pin "9") (pinfunction "3A_9") (pintype "unspecified"))
    )
    (net (code "35") (name "GND") (class "Default")
      (node (ref "12V") (pin "2") (pinfunction "2_2") (pintype "unspecified"))
      (node (ref "12V-INDICATOR") (pin "1") (pinfunction "-_1") (pintype "unspecified"))
      (node (ref "5V-FOR-LEDS") (pin "2") (pinfunction "2_2") (pintype "unspecified"))
      (node (ref "5V-INDICATOR") (pin "1") (pinfunction "-_1") (pintype "unspecified"))
      (node (ref "CAP-1-ANALOG-REF") (pin "2") (pinfunction "2_2") (pintype "unspecified"))
      (node (ref "CAP-2-ANALOG-REF") (pin "2") (pinfunction "2_2") (pintype "unspecified"))
      (node (ref "CAP-4-ANALOG-REF") (pin "2") (pinfunction "2_2") (pintype "unspecified"))
      (node (ref "CAP1-FOR-3.3V-PS") (pin "2") (pinfunction "2_2") (pintype "input"))
      (node (ref "CAP2-FOR-3.3V-PS") (pin "2") (pinfunction "2_2") (pintype "input"))
      (node (ref "CARD1") (pin "10") (pinfunction "G3_10") (pintype "input"))
      (node (ref "CARD1") (pin "11") (pinfunction "G4_11") (pintype "input"))
      (node (ref "CARD1") (pin "12") (pinfunction "G1_12") (pintype "input"))
      (node (ref "CARD1") (pin "13") (pinfunction "G2_13") (pintype "input"))
      (node (ref "CARD1") (pin "6") (pinfunction "VSS_6") (pintype "input"))
      (node (ref "CRYSTAL-CAP-1") (pin "1") (pinfunction "1_1") (pintype "input"))
      (node (ref "CRYSTAL-CAP-2") (pin "1") (pinfunction "1_1") (pintype "input"))
      (node (ref "DECODER-01-08") (pin "5") (pinfunction "E2#_5") (pintype "unspecified"))
      (node (ref "DECODER-01-08") (pin "8") (pinfunction "GND_8") (pintype "unspecified"))
      (node (ref "DECODER-09-16") (pin "5") (pinfunction "E2#_5") (pintype "unspecified"))
      (node (ref "DECODER-09-16") (pin "8") (pinfunction "GND_8") (pintype "unspecified"))
      (node (ref "DISPLAY") (pin "1") (pinfunction "1_1") (pintype "unspecified"))
      (node (ref "ENCODER-01-08") (pin "8") (pinfunction "GND_8") (pintype "unspecified"))
      (node (ref "ENCODER-09-16") (pin "5") (pinfunction "EI_5") (pintype "unspecified"))
      (node (ref "ENCODER-09-16") (pin "8") (pinfunction "GND_8") (pintype "unspecified"))
      (node (ref "H1") (pin "19") (pinfunction "19_19") (pintype "unspecified"))
      (node (ref "H1") (pin "20") (pinfunction "20_20") (pintype "unspecified"))
      (node (ref "H4") (pin "1") (pinfunction "1_1") (pintype "unspecified"))
      (node (ref "ICSP-PROGRAM") (pin "6") (pinfunction "6_6") (pintype "input"))
      (node (ref "PROG-BUTTON") (pin "3") (pinfunction "3_3") (pintype "unspecified"))
      (node (ref "PROG-BUTTON") (pin "4") (pinfunction "4_4") (pintype "unspecified"))
      (node (ref "U1") (pin "1") (pinfunction "GND/ADJ_1") (pintype "unspecified"))
      (node (ref "U3") (pin "21") (pinfunction "GND_21") (pintype "unspecified"))
      (node (ref "U3") (pin "3") (pinfunction "GND_3") (pintype "unspecified"))
      (node (ref "U3") (pin "5") (pinfunction "GND_5") (pintype "unspecified"))
      (node (ref "U5") (pin "7") (pinfunction "GND_7") (pintype "unspecified"))
      (node (ref "U6") (pin "7") (pinfunction "GND_7") (pintype "unspecified"))
      (node (ref "U7") (pin "2") (pinfunction "A1_2") (pintype "unspecified"))
      (node (ref "U7") (pin "3") (pinfunction "A2_3") (pintype "unspecified"))
      (node (ref "U7") (pin "4") (pinfunction "E1#_4") (pintype "unspecified"))
      (node (ref "U7") (pin "5") (pinfunction "E2#_5") (pintype "unspecified"))
      (node (ref "U7") (pin "8") (pinfunction "GND_8") (pintype "unspecified"))
      (node (ref "U8") (pin "7") (pinfunction "GND_7") (pintype "unspecified"))
      (node (ref "USB1") (pin "0") (pinfunction "MTN_0") (pintype "input"))
      (node (ref "USB1") (pin "5") (pinfunction "V-_5") (pintype "unspecified"))
      (node (ref "X2") (pin "2") (pinfunction "GND_2") (pintype "unspecified"))
      (node (ref "X2") (pin "4") (pinfunction "GND_4") (pintype "unspecified"))
    )
    (net (code "36") (name "ICSP-MISO") (class "Default")
      (node (ref "ICSP-PROGRAM") (pin "1") (pinfunction "1_1") (pintype "input"))
      (node (ref "U3") (pin "16") (pinfunction "(PCINT4/MISO)PB4_16") (pintype "unspecified"))
      (node (ref "U6") (pin "13") (pinfunction "B1_13") (pintype "unspecified"))
    )
    (net (code "37") (name "ICSP-MOSI") (class "Default")
      (node (ref "ICSP-PROGRAM") (pin "4") (pinfunction "4_4") (pintype "input"))
      (node (ref "RN9") (pin "2") (pinfunction "2_2") (pintype "input"))
      (node (ref "U3") (pin "15") (pinfunction "(PCINT3/OC2A/MOSI)PB3_15") (pintype "unspecified"))
      (node (ref "U6") (pin "11") (pinfunction "B3_11") (pintype "unspecified"))
    )
    (net (code "38") (name "ICSP-RESET") (class "Default")
      (node (ref "ICSP-PROGRAM") (pin "5") (pinfunction "5_5") (pintype "input"))
      (node (ref "RN9") (pin "4") (pinfunction "4_4") (pintype "input"))
      (node (ref "U3") (pin "29") (pinfunction "PC6(RESET#/PCINT14)_29") (pintype "unspecified"))
      (node (ref "U8") (pin "1") (pinfunction "1A_1") (pintype "unspecified"))
    )
    (net (code "39") (name "ICSP-SCK") (class "Default")
      (node (ref "ICSP-PROGRAM") (pin "3") (pinfunction "3_3") (pintype "input"))
      (node (ref "U3") (pin "17") (pinfunction "PB5(SCK/PCINT5)_17") (pintype "unspecified"))
      (node (ref "U6") (pin "12") (pinfunction "B2_12") (pintype "unspecified"))
    )
    (net (code "40") (name "INP-00") (class "Default")
      (node (ref "U3") (pin "25") (pinfunction "PC2(ADC2/PCINT10)_25") (pintype "unspecified"))
      (node (ref "U5") (pin "11") (pinfunction "4Y_11") (pintype "unspecified"))
    )
    (net (code "41") (name "INP-01") (class "Default")
      (node (ref "U3") (pin "26") (pinfunction "PC3(ADC3/PCINT11)_26") (pintype "unspecified"))
      (node (ref "U5") (pin "3") (pinfunction "1Y_3") (pintype "unspecified"))
    )
    (net (code "42") (name "INP-02") (class "Default")
      (node (ref "U3") (pin "2") (pinfunction "(PCINT20/XCK/T0)PD4_2") (pintype "unspecified"))
      (node (ref "U3") (pin "23") (pinfunction "PC0(ADC0/PCINT8)_23") (pintype "unspecified"))
      (node (ref "U5") (pin "6") (pinfunction "2Y_6") (pintype "unspecified"))
    )
    (net (code "43") (name "INP-ACTIVITY") (class "Default")
      (node (ref "U3") (pin "31") (pinfunction "PD1(TXD/PCINT17)_31") (pintype "unspecified"))
      (node (ref "U5") (pin "8") (pinfunction "3Y_8") (pintype "unspecified"))
    )
    (net (code "44") (name "Net-(5V-INDICATOR-+)") (class "Default")
      (node (ref "5V-INDICATOR") (pin "2") (pinfunction "+_2") (pintype "unspecified"))
      (node (ref "R-4-5V-INDICATOR") (pin "2") (pinfunction "2_2") (pintype "input"))
    )
    (net (code "45") (name "Net-(12V-INDICATOR-+)") (class "Default")
      (node (ref "12V-INDICATOR") (pin "2") (pinfunction "+_2") (pintype "unspecified"))
      (node (ref "R-4-12V-INDICATOR") (pin "2") (pinfunction "2_2") (pintype "input"))
    )
    (net (code "46") (name "OPP-RESET") (class "Default")
      (node (ref "U6") (pin "10") (pinfunction "B4_10") (pintype "unspecified"))
      (node (ref "U8") (pin "2") (pinfunction "1Y_2") (pintype "unspecified"))
    )
    (net (code "47") (name "OUT-00") (class "Default")
      (node (ref "DECODER-01-08") (pin "1") (pinfunction "A0_1") (pintype "unspecified"))
      (node (ref "DECODER-09-16") (pin "1") (pinfunction "A0_1") (pintype "unspecified"))
      (node (ref "U3") (pin "14") (pinfunction "(PCINT2/SS#/OC1B)PB2_14") (pintype "unspecified"))
    )
    (net (code "48") (name "OUT-01") (class "Default")
      (node (ref "DECODER-01-08") (pin "2") (pinfunction "A1_2") (pintype "unspecified"))
      (node (ref "DECODER-09-16") (pin "2") (pinfunction "A1_2") (pintype "unspecified"))
      (node (ref "U3") (pin "13") (pinfunction "(PCINT1/OC1A)PB1_13") (pintype "unspecified"))
    )
    (net (code "49") (name "OUT-02") (class "Default")
      (node (ref "DECODER-01-08") (pin "3") (pinfunction "A2_3") (pintype "unspecified"))
      (node (ref "DECODER-09-16") (pin "3") (pinfunction "A2_3") (pintype "unspecified"))
      (node (ref "U3") (pin "12") (pinfunction "(PCINT0/CLKO/ICP1)PB0_12") (pintype "unspecified"))
    )
    (net (code "50") (name "OUT-03") (class "Default")
      (node (ref "U3") (pin "11") (pinfunction "(PCINT23/AIN1)PD7_11") (pintype "unspecified"))
      (node (ref "U7") (pin "1") (pinfunction "A0_1") (pintype "unspecified"))
    )
    (net (code "51") (name "RELAY-01") (class "Default")
      (node (ref "DECODER-01-08") (pin "15") (pinfunction "Y0#_15") (pintype "unspecified"))
      (node (ref "H1") (pin "3") (pinfunction "3_3") (pintype "unspecified"))
    )
    (net (code "52") (name "RELAY-02") (class "Default")
      (node (ref "DECODER-01-08") (pin "14") (pinfunction "Y1#_14") (pintype "unspecified"))
      (node (ref "H1") (pin "4") (pinfunction "4_4") (pintype "unspecified"))
    )
    (net (code "53") (name "RELAY-03") (class "Default")
      (node (ref "DECODER-01-08") (pin "13") (pinfunction "Y2#_13") (pintype "unspecified"))
      (node (ref "H1") (pin "5") (pinfunction "5_5") (pintype "unspecified"))
    )
    (net (code "54") (name "RELAY-04") (class "Default")
      (node (ref "DECODER-01-08") (pin "12") (pinfunction "Y3#_12") (pintype "unspecified"))
      (node (ref "H1") (pin "6") (pinfunction "6_6") (pintype "unspecified"))
    )
    (net (code "55") (name "RELAY-05") (class "Default")
      (node (ref "DECODER-01-08") (pin "11") (pinfunction "Y4#_11") (pintype "unspecified"))
      (node (ref "H1") (pin "7") (pinfunction "7_7") (pintype "unspecified"))
    )
    (net (code "56") (name "RELAY-06") (class "Default")
      (node (ref "DECODER-01-08") (pin "10") (pinfunction "Y5#_10") (pintype "unspecified"))
      (node (ref "H1") (pin "8") (pinfunction "8_8") (pintype "unspecified"))
    )
    (net (code "57") (name "RELAY-07") (class "Default")
      (node (ref "DECODER-01-08") (pin "9") (pinfunction "Y6#_9") (pintype "unspecified"))
      (node (ref "H1") (pin "9") (pinfunction "9_9") (pintype "unspecified"))
    )
    (net (code "58") (name "RELAY-08") (class "Default")
      (node (ref "DECODER-01-08") (pin "7") (pinfunction "Y7#_7") (pintype "unspecified"))
      (node (ref "H1") (pin "10") (pinfunction "10_10") (pintype "unspecified"))
    )
    (net (code "59") (name "RELAY-09") (class "Default")
      (node (ref "DECODER-09-16") (pin "15") (pinfunction "Y0#_15") (pintype "unspecified"))
      (node (ref "H1") (pin "11") (pinfunction "11_11") (pintype "unspecified"))
    )
    (net (code "60") (name "RELAY-10") (class "Default")
      (node (ref "DECODER-09-16") (pin "14") (pinfunction "Y1#_14") (pintype "unspecified"))
      (node (ref "H1") (pin "12") (pinfunction "12_12") (pintype "unspecified"))
    )
    (net (code "61") (name "RELAY-11") (class "Default")
      (node (ref "DECODER-09-16") (pin "13") (pinfunction "Y2#_13") (pintype "unspecified"))
      (node (ref "H1") (pin "13") (pinfunction "13_13") (pintype "unspecified"))
    )
    (net (code "62") (name "RELAY-12") (class "Default")
      (node (ref "DECODER-09-16") (pin "12") (pinfunction "Y3#_12") (pintype "unspecified"))
      (node (ref "H1") (pin "14") (pinfunction "14_14") (pintype "unspecified"))
    )
    (net (code "63") (name "RELAY-13") (class "Default")
      (node (ref "DECODER-09-16") (pin "11") (pinfunction "Y4#_11") (pintype "unspecified"))
      (node (ref "H1") (pin "15") (pinfunction "15_15") (pintype "unspecified"))
    )
    (net (code "64") (name "RELAY-14") (class "Default")
      (node (ref "DECODER-09-16") (pin "10") (pinfunction "Y5#_10") (pintype "unspecified"))
      (node (ref "H1") (pin "16") (pinfunction "16_16") (pintype "unspecified"))
    )
    (net (code "65") (name "RELAY-15") (class "Default")
      (node (ref "DECODER-09-16") (pin "9") (pinfunction "Y6#_9") (pintype "unspecified"))
      (node (ref "H1") (pin "17") (pinfunction "17_17") (pintype "unspecified"))
    )
    (net (code "66") (name "RELAY-16") (class "Default")
      (node (ref "DECODER-09-16") (pin "7") (pinfunction "Y7#_7") (pintype "unspecified"))
      (node (ref "H1") (pin "18") (pinfunction "18_18") (pintype "unspecified"))
    )
    (net (code "67") (name "SCL") (class "Default")
      (node (ref "DISPLAY") (pin "4") (pinfunction "4_4") (pintype "unspecified"))
      (node (ref "U3") (pin "28") (pinfunction "PC5(ADC5/SCL/PCINT13)_28") (pintype "unspecified"))
    )
    (net (code "68") (name "SD-PIN-2") (class "Default")
      (node (ref "CARD1") (pin "2") (pinfunction "CD/DAT3_2") (pintype "input"))
      (node (ref "U6") (pin "5") (pinfunction "A4_5") (pintype "unspecified"))
    )
    (net (code "69") (name "SD-PIN-3") (class "Default")
      (node (ref "CARD1") (pin "3") (pinfunction "CMD_3") (pintype "input"))
      (node (ref "U6") (pin "4") (pinfunction "A3_4") (pintype "unspecified"))
    )
    (net (code "70") (name "SD-PIN-5") (class "Default")
      (node (ref "CARD1") (pin "5") (pinfunction "CLK_5") (pintype "input"))
      (node (ref "U6") (pin "3") (pinfunction "A2_3") (pintype "unspecified"))
    )
    (net (code "71") (name "SD-PIN-7") (class "Default")
      (node (ref "CARD1") (pin "7") (pinfunction "DAT0_7") (pintype "input"))
      (node (ref "U6") (pin "2") (pinfunction "A1_2") (pintype "unspecified"))
    )
    (net (code "72") (name "SDA") (class "Default")
      (node (ref "DISPLAY") (pin "3") (pinfunction "3_3") (pintype "unspecified"))
      (node (ref "U3") (pin "27") (pinfunction "PC4(ADC4/SDA/PCINT12)_27") (pintype "unspecified"))
    )
    (net (code "73") (name "XTAL1") (class "Default")
      (node (ref "CRYSTAL-CAP-1") (pin "2") (pinfunction "2_2") (pintype "input"))
      (node (ref "U3") (pin "7") (pinfunction "(PCINT6/XTAL1/TOSC1)PB6_7") (pintype "unspecified"))
      (node (ref "X2") (pin "3") (pinfunction "OSC2_3") (pintype "unspecified"))
    )
    (net (code "74") (name "XTAL2") (class "Default")
      (node (ref "CRYSTAL-CAP-2") (pin "2") (pinfunction "2_2") (pintype "input"))
      (node (ref "U3") (pin "8") (pinfunction "(PCINT7/XTAL2/TOSC2)PB7_8") (pintype "unspecified"))
      (node (ref "X2") (pin "1") (pinfunction "OSC1_1") (pintype "unspecified"))
    )
    (net (code "75") (name "unconnected-(CARD1-CD-Pad9)") (class "Default")
      (node (ref "CARD1") (pin "9") (pinfunction "CD_9") (pintype "input+no_connect"))
    )
    (net (code "76") (name "unconnected-(CARD1-DAT1-Pad8)") (class "Default")
      (node (ref "CARD1") (pin "8") (pinfunction "DAT1_8") (pintype "input+no_connect"))
    )
    (net (code "77") (name "unconnected-(CARD1-DAT2-Pad1)") (class "Default")
      (node (ref "CARD1") (pin "1") (pinfunction "DAT2_1") (pintype "input+no_connect"))
    )
    (net (code "78") (name "unconnected-(ENCODER-01-08-EO-Pad15)") (class "Default")
      (node (ref "ENCODER-01-08") (pin "15") (pinfunction "EO_15") (pintype "unspecified+no_connect"))
    )
    (net (code "79") (name "unconnected-(U3-ADC6-Pad19)") (class "Default")
      (node (ref "U3") (pin "19") (pinfunction "ADC6_19") (pintype "unspecified+no_connect"))
    )
    (net (code "80") (name "unconnected-(U3-ADC7-Pad22)") (class "Default")
      (node (ref "U3") (pin "22") (pinfunction "ADC7_22") (pintype "unspecified+no_connect"))
    )
    (net (code "81") (name "unconnected-(U3-PD0(RXD{slash}PCINT16)-Pad30)") (class "Default")
      (node (ref "U3") (pin "30") (pinfunction "PD0(RXD/PCINT16)_30") (pintype "unspecified+no_connect"))
    )
    (net (code "82") (name "unconnected-(U6-NC-Pad6)") (class "Default")
      (node (ref "U6") (pin "6") (pinfunction "NC_6") (pintype "unspecified+no_connect"))
    )
    (net (code "83") (name "unconnected-(U6-NC-Pad9)") (class "Default")
      (node (ref "U6") (pin "9") (pinfunction "NC_9") (pintype "unspecified+no_connect"))
    )
    (net (code "84") (name "unconnected-(U7-Y2#-Pad13)") (class "Default")
      (node (ref "U7") (pin "13") (pinfunction "Y2#_13") (pintype "unspecified+no_connect"))
    )
    (net (code "85") (name "unconnected-(U7-Y3#-Pad12)") (class "Default")
      (node (ref "U7") (pin "12") (pinfunction "Y3#_12") (pintype "unspecified+no_connect"))
    )
    (net (code "86") (name "unconnected-(U7-Y4#-Pad11)") (class "Default")
      (node (ref "U7") (pin "11") (pinfunction "Y4#_11") (pintype "unspecified+no_connect"))
    )
    (net (code "87") (name "unconnected-(U7-Y5#-Pad10)") (class "Default")
      (node (ref "U7") (pin "10") (pinfunction "Y5#_10") (pintype "unspecified+no_connect"))
    )
    (net (code "88") (name "unconnected-(U7-Y6#-Pad9)") (class "Default")
      (node (ref "U7") (pin "9") (pinfunction "Y6#_9") (pintype "unspecified+no_connect"))
    )
    (net (code "89") (name "unconnected-(U7-Y7#-Pad7)") (class "Default")
      (node (ref "U7") (pin "7") (pinfunction "Y7#_7") (pintype "unspecified+no_connect"))
    )
    (net (code "90") (name "unconnected-(U8-2A-Pad3)") (class "Default")
      (node (ref "U8") (pin "3") (pinfunction "2A_3") (pintype "unspecified+no_connect"))
    )
    (net (code "91") (name "unconnected-(U8-2Y-Pad4)") (class "Default")
      (node (ref "U8") (pin "4") (pinfunction "2Y_4") (pintype "unspecified+no_connect"))
    )
    (net (code "92") (name "unconnected-(U8-3A-Pad5)") (class "Default")
      (node (ref "U8") (pin "5") (pinfunction "3A_5") (pintype "unspecified+no_connect"))
    )
    (net (code "93") (name "unconnected-(U8-3Y-Pad6)") (class "Default")
      (node (ref "U8") (pin "6") (pinfunction "3Y_6") (pintype "unspecified+no_connect"))
    )
    (net (code "94") (name "unconnected-(U8-4A-Pad9)") (class "Default")
      (node (ref "U8") (pin "9") (pinfunction "4A_9") (pintype "unspecified+no_connect"))
    )
    (net (code "95") (name "unconnected-(U8-4Y-Pad8)") (class "Default")
      (node (ref "U8") (pin "8") (pinfunction "4Y_8") (pintype "unspecified+no_connect"))
    )
    (net (code "96") (name "unconnected-(U8-5A-Pad11)") (class "Default")
      (node (ref "U8") (pin "11") (pinfunction "5A_11") (pintype "unspecified+no_connect"))
    )
    (net (code "97") (name "unconnected-(U8-5Y-Pad10)") (class "Default")
      (node (ref "U8") (pin "10") (pinfunction "5Y_10") (pintype "unspecified+no_connect"))
    )
    (net (code "98") (name "unconnected-(U8-6A-Pad13)") (class "Default")
      (node (ref "U8") (pin "13") (pinfunction "6A_13") (pintype "unspecified+no_connect"))
    )
    (net (code "99") (name "unconnected-(U8-6Y-Pad12)") (class "Default")
      (node (ref "U8") (pin "12") (pinfunction "6Y_12") (pintype "unspecified+no_connect"))
    )
    (net (code "100") (name "unconnected-(USB1-D+-Pad3)") (class "Default")
      (node (ref "USB1") (pin "3") (pinfunction "D+_3") (pintype "unspecified+no_connect"))
    )
    (net (code "101") (name "unconnected-(USB1-D--Pad2)") (class "Default")
      (node (ref "USB1") (pin "2") (pinfunction "D-_2") (pintype "unspecified+no_connect"))
    )
    (net (code "102") (name "unconnected-(USB1-ID-Pad4)") (class "Default")
      (node (ref "USB1") (pin "4") (pinfunction "ID_4") (pintype "unspecified+no_connect"))
    )
  )
)
